# RF08.net
KiCad netlist of a schematic drawn in EAGLE
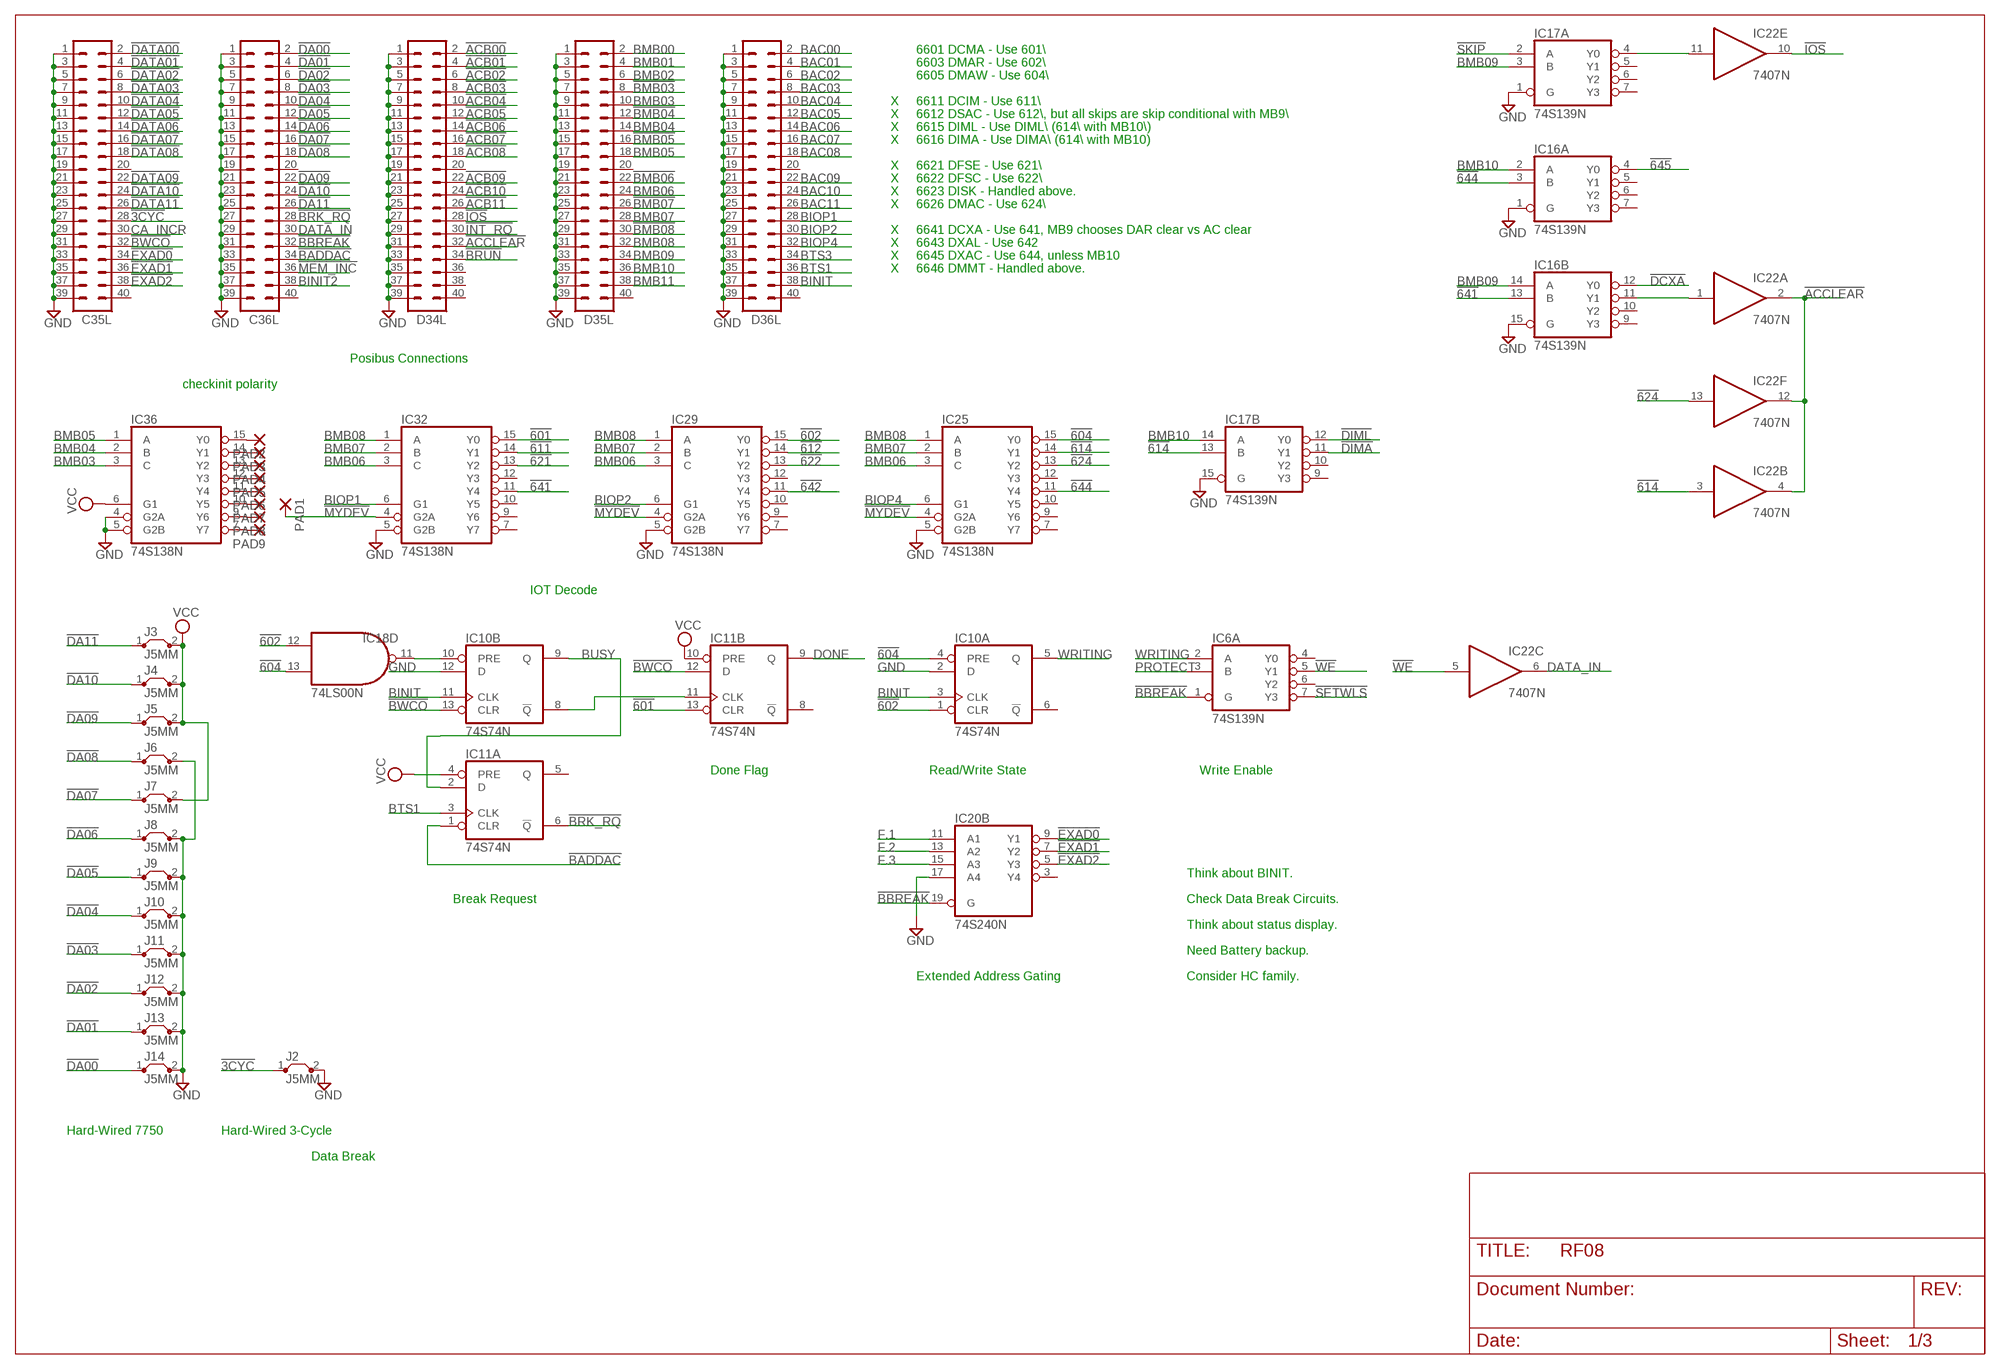
[diagram p0: schematic, sheet 1]
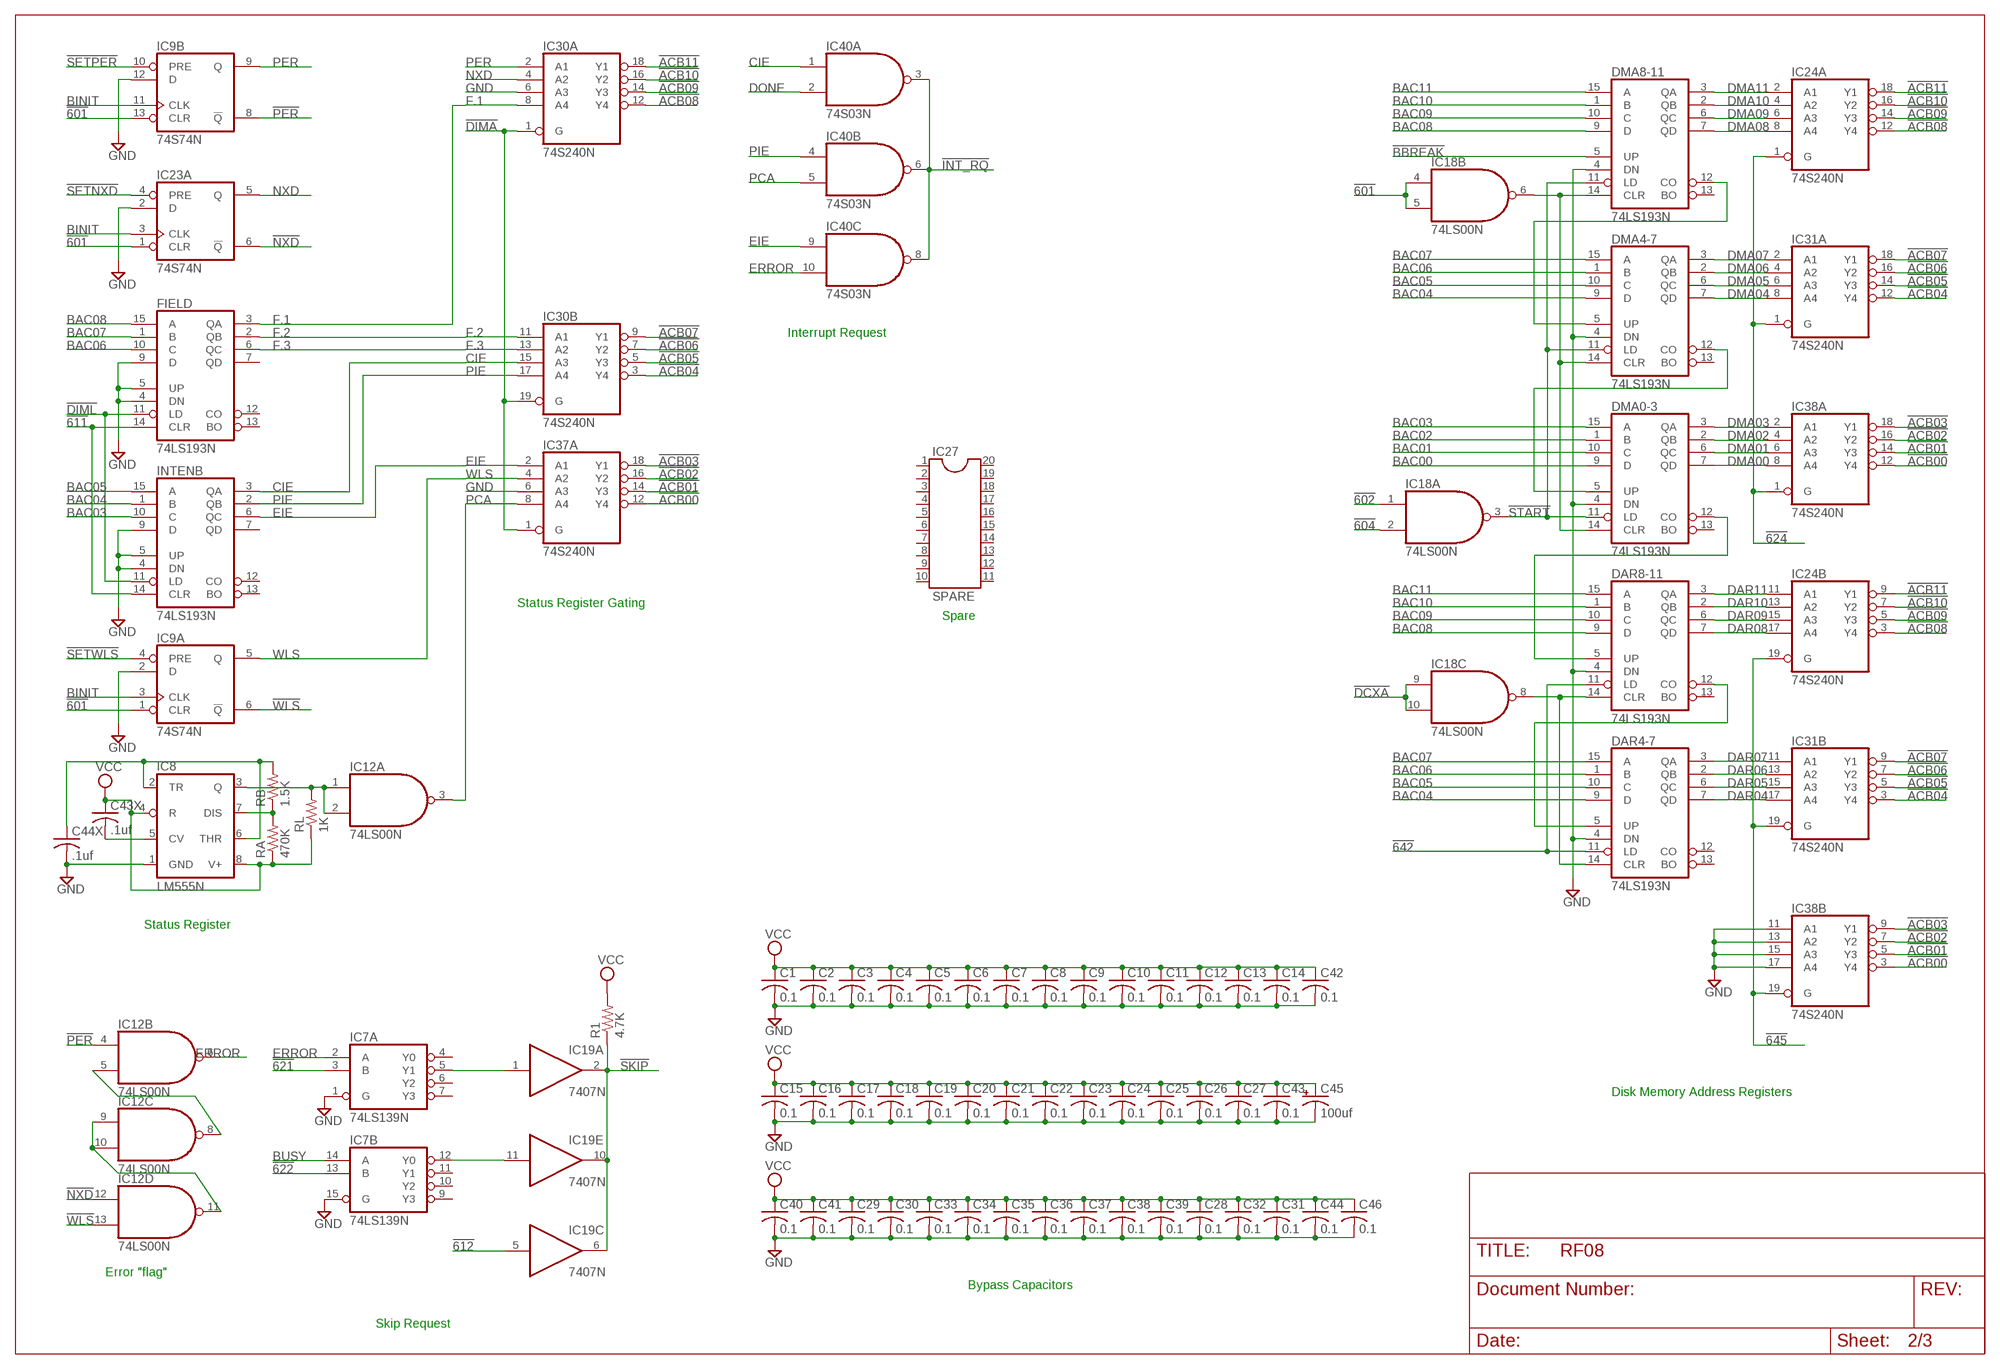
[diagram p1: schematic, sheet 2]
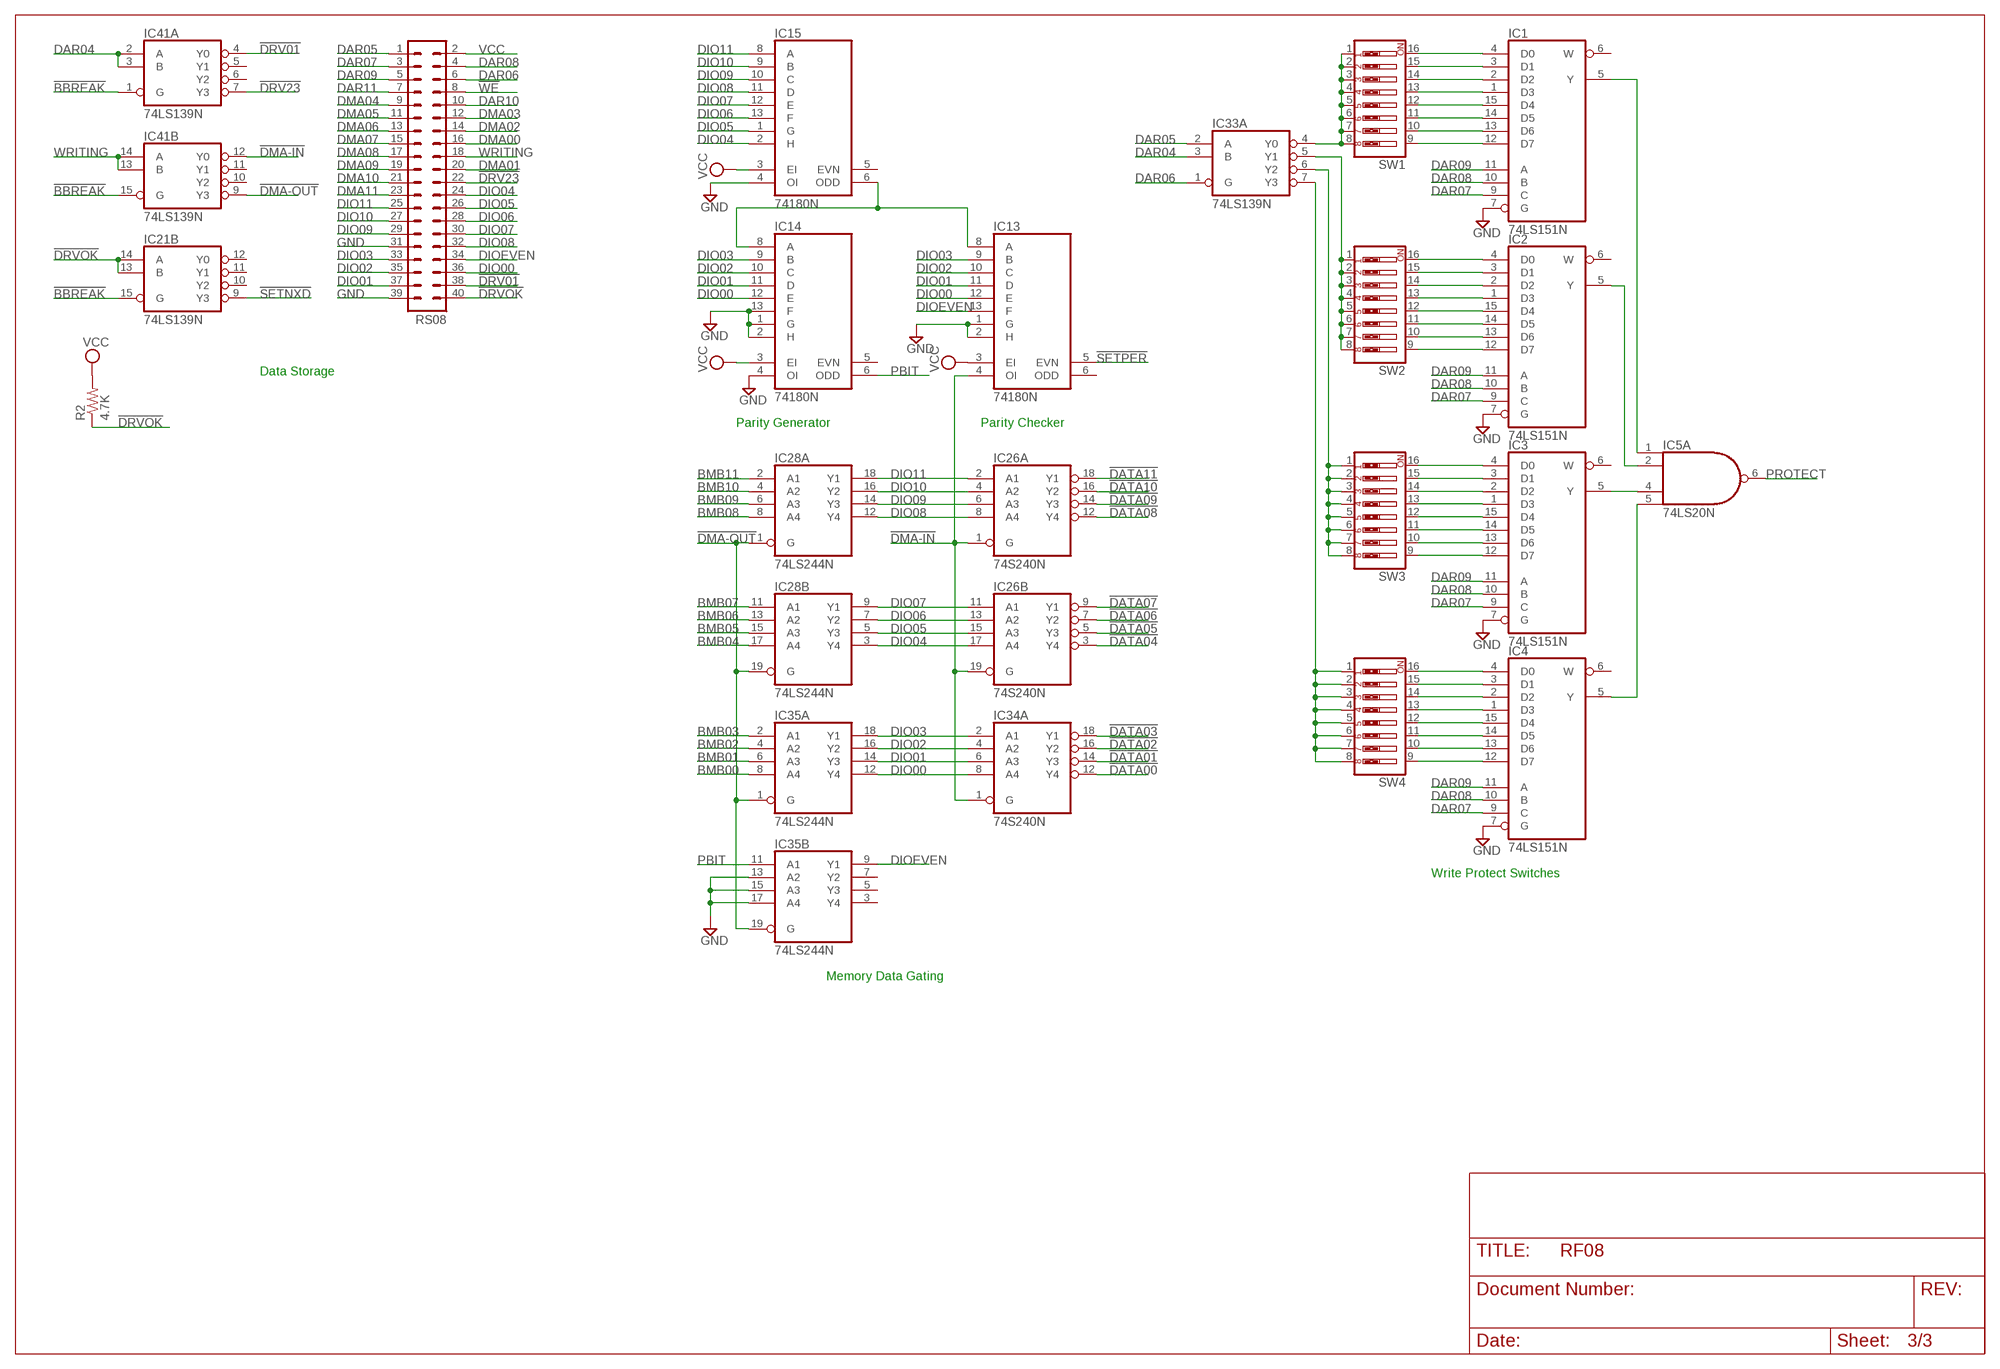
[diagram p2: schematic, sheet 3]

(export (version "E")
  (design (tool "Eeschema 10.0.6"))
  (components
    (comp (ref "C1")
      (value "0.1")
      (footprint "eagle-import:C050-025X075")
      (libsource (lib "eagle-import") (part "C-US050-025X075"))
    )
    (comp (ref "C2")
      (value "0.1")
      (footprint "eagle-import:C050-025X075")
      (libsource (lib "eagle-import") (part "C-US050-025X075"))
    )
    (comp (ref "C3")
      (value "0.1")
      (footprint "eagle-import:C050-025X075")
      (libsource (lib "eagle-import") (part "C-US050-025X075"))
    )
    (comp (ref "C4")
      (value "0.1")
      (footprint "eagle-import:C050-025X075")
      (libsource (lib "eagle-import") (part "C-US050-025X075"))
    )
    (comp (ref "C5")
      (value "0.1")
      (footprint "eagle-import:C050-025X075")
      (libsource (lib "eagle-import") (part "C-US050-025X075"))
    )
    (comp (ref "C6")
      (value "0.1")
      (footprint "eagle-import:C050-025X075")
      (libsource (lib "eagle-import") (part "C-US050-025X075"))
    )
    (comp (ref "C7")
      (value "0.1")
      (footprint "eagle-import:C050-025X075")
      (libsource (lib "eagle-import") (part "C-US050-025X075"))
    )
    (comp (ref "C8")
      (value "0.1")
      (footprint "eagle-import:C050-025X075")
      (libsource (lib "eagle-import") (part "C-US050-025X075"))
    )
    (comp (ref "C9")
      (value "0.1")
      (footprint "eagle-import:C050-025X075")
      (libsource (lib "eagle-import") (part "C-US050-025X075"))
    )
    (comp (ref "C10")
      (value "0.1")
      (footprint "eagle-import:C050-025X075")
      (libsource (lib "eagle-import") (part "C-US050-025X075"))
    )
    (comp (ref "C11")
      (value "0.1")
      (footprint "eagle-import:C050-025X075")
      (libsource (lib "eagle-import") (part "C-US050-025X075"))
    )
    (comp (ref "C12")
      (value "0.1")
      (footprint "eagle-import:C050-025X075")
      (libsource (lib "eagle-import") (part "C-US050-025X075"))
    )
    (comp (ref "C13")
      (value "0.1")
      (footprint "eagle-import:C050-025X075")
      (libsource (lib "eagle-import") (part "C-US050-025X075"))
    )
    (comp (ref "C14")
      (value "0.1")
      (footprint "eagle-import:C050-025X075")
      (libsource (lib "eagle-import") (part "C-US050-025X075"))
    )
    (comp (ref "C15")
      (value "0.1")
      (footprint "eagle-import:C050-025X075")
      (libsource (lib "eagle-import") (part "C-US050-025X075"))
    )
    (comp (ref "C16")
      (value "0.1")
      (footprint "eagle-import:C050-025X075")
      (libsource (lib "eagle-import") (part "C-US050-025X075"))
    )
    (comp (ref "C17")
      (value "0.1")
      (footprint "eagle-import:C050-025X075")
      (libsource (lib "eagle-import") (part "C-US050-025X075"))
    )
    (comp (ref "C18")
      (value "0.1")
      (footprint "eagle-import:C050-025X075")
      (libsource (lib "eagle-import") (part "C-US050-025X075"))
    )
    (comp (ref "C19")
      (value "0.1")
      (footprint "eagle-import:C050-025X075")
      (libsource (lib "eagle-import") (part "C-US050-025X075"))
    )
    (comp (ref "C20")
      (value "0.1")
      (footprint "eagle-import:C050-025X075")
      (libsource (lib "eagle-import") (part "C-US050-025X075"))
    )
    (comp (ref "C21")
      (value "0.1")
      (footprint "eagle-import:C050-025X075")
      (libsource (lib "eagle-import") (part "C-US050-025X075"))
    )
    (comp (ref "C22")
      (value "0.1")
      (footprint "eagle-import:C050-025X075")
      (libsource (lib "eagle-import") (part "C-US050-025X075"))
    )
    (comp (ref "C23")
      (value "0.1")
      (footprint "eagle-import:C050-025X075")
      (libsource (lib "eagle-import") (part "C-US050-025X075"))
    )
    (comp (ref "C24")
      (value "0.1")
      (footprint "eagle-import:C050-025X075")
      (libsource (lib "eagle-import") (part "C-US050-025X075"))
    )
    (comp (ref "C25")
      (value "0.1")
      (footprint "eagle-import:C050-025X075")
      (libsource (lib "eagle-import") (part "C-US050-025X075"))
    )
    (comp (ref "C26")
      (value "0.1")
      (footprint "eagle-import:C050-025X075")
      (libsource (lib "eagle-import") (part "C-US050-025X075"))
    )
    (comp (ref "C27")
      (value "0.1")
      (footprint "eagle-import:C050-025X075")
      (libsource (lib "eagle-import") (part "C-US050-025X075"))
    )
    (comp (ref "C28")
      (value "0.1")
      (footprint "eagle-import:C050-025X075")
      (libsource (lib "eagle-import") (part "C-US050-025X075"))
    )
    (comp (ref "C29")
      (value "0.1")
      (footprint "eagle-import:C050-025X075")
      (libsource (lib "eagle-import") (part "C-US050-025X075"))
    )
    (comp (ref "C30")
      (value "0.1")
      (footprint "eagle-import:C050-025X075")
      (libsource (lib "eagle-import") (part "C-US050-025X075"))
    )
    (comp (ref "C31")
      (value "0.1")
      (footprint "eagle-import:C050-025X075")
      (libsource (lib "eagle-import") (part "C-US050-025X075"))
    )
    (comp (ref "C32")
      (value "0.1")
      (footprint "eagle-import:C050-025X075")
      (libsource (lib "eagle-import") (part "C-US050-025X075"))
    )
    (comp (ref "C33")
      (value "0.1")
      (footprint "eagle-import:C050-025X075")
      (libsource (lib "eagle-import") (part "C-US050-025X075"))
    )
    (comp (ref "C34")
      (value "0.1")
      (footprint "eagle-import:C050-025X075")
      (libsource (lib "eagle-import") (part "C-US050-025X075"))
    )
    (comp (ref "C35")
      (value "0.1")
      (footprint "eagle-import:C050-025X075")
      (libsource (lib "eagle-import") (part "C-US050-025X075"))
    )
    (comp (ref "C36")
      (value "0.1")
      (footprint "eagle-import:C050-025X075")
      (libsource (lib "eagle-import") (part "C-US050-025X075"))
    )
    (comp (ref "C37")
      (value "0.1")
      (footprint "eagle-import:C050-025X075")
      (libsource (lib "eagle-import") (part "C-US050-025X075"))
    )
    (comp (ref "C38")
      (value "0.1")
      (footprint "eagle-import:C050-025X075")
      (libsource (lib "eagle-import") (part "C-US050-025X075"))
    )
    (comp (ref "C39")
      (value "0.1")
      (footprint "eagle-import:C050-025X075")
      (libsource (lib "eagle-import") (part "C-US050-025X075"))
    )
    (comp (ref "C40")
      (value "0.1")
      (footprint "eagle-import:C050-025X075")
      (libsource (lib "eagle-import") (part "C-US050-025X075"))
    )
    (comp (ref "C41")
      (value "0.1")
      (footprint "eagle-import:C050-025X075")
      (libsource (lib "eagle-import") (part "C-US050-025X075"))
    )
    (comp (ref "C42")
      (value "0.1")
      (footprint "eagle-import:C050-025X075")
      (libsource (lib "eagle-import") (part "C-US050-025X075"))
    )
    (comp (ref "C43")
      (value "0.1")
      (footprint "eagle-import:C050-025X075")
      (libsource (lib "eagle-import") (part "C-US050-025X075"))
    )
    (comp (ref "C43X")
      (value ".1uf")
      (footprint "eagle-import:C050-025X075")
      (libsource (lib "eagle-import") (part "C-US050-025X075"))
    )
    (comp (ref "C44")
      (value "0.1")
      (footprint "eagle-import:C050-025X075")
      (libsource (lib "eagle-import") (part "C-US050-025X075"))
    )
    (comp (ref "C44X")
      (value ".1uf")
      (footprint "eagle-import:C050-025X075")
      (libsource (lib "eagle-import") (part "C-US050-025X075"))
    )
    (comp (ref "C45")
      (value "100uf")
      (footprint "eagle-import:E22-6")
      (libsource (lib "eagle-import") (part "CPOL-USE22-6AXIAL"))
    )
    (comp (ref "C46")
      (value "0.1")
      (footprint "eagle-import:C050-025X075")
      (libsource (lib "eagle-import") (part "C-US050-025X075"))
    )
    (comp (ref "DAR4-7")
      (value "74LS193N")
      (footprint "eagle-import:DIL16")
      (libsource (lib "eagle-import") (part "74192NLS"))
    )
    (comp (ref "DAR8-11")
      (value "74LS193N")
      (footprint "eagle-import:DIL16")
      (libsource (lib "eagle-import") (part "74192NLS"))
    )
    (comp (ref "DMA0-3")
      (value "74LS193N")
      (footprint "eagle-import:DIL16")
      (libsource (lib "eagle-import") (part "74192NLS"))
    )
    (comp (ref "DMA4-7")
      (value "74LS193N")
      (footprint "eagle-import:DIL16")
      (libsource (lib "eagle-import") (part "74192NLS"))
    )
    (comp (ref "DMA8-11")
      (value "74LS193N")
      (footprint "eagle-import:DIL16")
      (libsource (lib "eagle-import") (part "74192NLS"))
    )
    (comp (ref "FIELD")
      (value "74LS193N")
      (footprint "eagle-import:DIL16")
      (libsource (lib "eagle-import") (part "74192NLS"))
    )
    (comp (ref "IC7")
      (value "74LS139N")
      (footprint "eagle-import:DIL16")
      (libsource (lib "eagle-import") (part "74139NLS"))
    )
    (comp (ref "IC8")
      (value "LM555N")
      (footprint "eagle-import:DIL08")
      (libsource (lib "eagle-import") (part "555NLM"))
    )
    (comp (ref "IC9")
      (value "74S74N")
      (footprint "eagle-import:DIL14")
      (libsource (lib "eagle-import") (part "7474NS"))
    )
    (comp (ref "IC12")
      (value "74LS00N")
      (footprint "eagle-import:DIL14")
      (libsource (lib "eagle-import") (part "7400NLS"))
    )
    (comp (ref "IC18")
      (value "74LS00N")
      (footprint "eagle-import:DIL14")
      (libsource (lib "eagle-import") (part "7400NLS"))
    )
    (comp (ref "IC19")
      (value "7407N")
      (footprint "eagle-import:DIL14")
      (libsource (lib "eagle-import") (part "7407N"))
    )
    (comp (ref "IC23")
      (value "74S74N")
      (footprint "eagle-import:DIL14")
      (libsource (lib "eagle-import") (part "7474NS"))
    )
    (comp (ref "IC24")
      (value "74S240N")
      (footprint "eagle-import:DIL20")
      (libsource (lib "eagle-import") (part "74240NS"))
    )
    (comp (ref "IC27")
      (value "SPARE")
      (footprint "eagle-import:DIL20")
      (libsource (lib "eagle-import") (part "DIL20"))
    )
    (comp (ref "IC30")
      (value "74S240N")
      (footprint "eagle-import:DIL20")
      (libsource (lib "eagle-import") (part "74240NS"))
    )
    (comp (ref "IC31")
      (value "74S240N")
      (footprint "eagle-import:DIL20")
      (libsource (lib "eagle-import") (part "74240NS"))
    )
    (comp (ref "IC37")
      (value "74S240N")
      (footprint "eagle-import:DIL20")
      (libsource (lib "eagle-import") (part "74240NS"))
    )
    (comp (ref "IC38")
      (value "74S240N")
      (footprint "eagle-import:DIL20")
      (libsource (lib "eagle-import") (part "74240NS"))
    )
    (comp (ref "IC40")
      (value "74S03N")
      (footprint "eagle-import:DIL14")
      (libsource (lib "eagle-import") (part "7403NS"))
    )
    (comp (ref "INTENB")
      (value "74LS193N")
      (footprint "eagle-import:DIL16")
      (libsource (lib "eagle-import") (part "74192NLS"))
    )
    (comp (ref "R1")
      (value "4.7K")
      (footprint "eagle-import:0207_10")
      (libsource (lib "eagle-import") (part "R-US_0207/10"))
    )
    (comp (ref "RA")
      (value "470K")
      (footprint "eagle-import:0207_10")
      (libsource (lib "eagle-import") (part "R-US_0207/10"))
    )
    (comp (ref "RB")
      (value "1.5K")
      (footprint "eagle-import:0207_10")
      (libsource (lib "eagle-import") (part "R-US_0207/10"))
    )
    (comp (ref "RL")
      (value "1K")
      (footprint "eagle-import:0207_10")
      (libsource (lib "eagle-import") (part "R-US_0207/10"))
    )
    (comp (ref "IC1")
      (value "74LS151N")
      (footprint "eagle-import:DIL16")
      (libsource (lib "eagle-import") (part "74151NLS"))
    )
    (comp (ref "IC2")
      (value "74LS151N")
      (footprint "eagle-import:DIL16")
      (libsource (lib "eagle-import") (part "74151NLS"))
    )
    (comp (ref "IC3")
      (value "74LS151N")
      (footprint "eagle-import:DIL16")
      (libsource (lib "eagle-import") (part "74151NLS"))
    )
    (comp (ref "IC4")
      (value "74LS151N")
      (footprint "eagle-import:DIL16")
      (libsource (lib "eagle-import") (part "74151NLS"))
    )
    (comp (ref "IC5")
      (value "74LS20N")
      (footprint "eagle-import:DIL14")
      (libsource (lib "eagle-import") (part "7420NLS"))
    )
    (comp (ref "IC13")
      (value "74180N")
      (footprint "eagle-import:DIL14")
      (libsource (lib "eagle-import") (part "74180N"))
    )
    (comp (ref "IC14")
      (value "74180N")
      (footprint "eagle-import:DIL14")
      (libsource (lib "eagle-import") (part "74180N"))
    )
    (comp (ref "IC15")
      (value "74180N")
      (footprint "eagle-import:DIL14")
      (libsource (lib "eagle-import") (part "74180N"))
    )
    (comp (ref "IC21")
      (value "74LS139N")
      (footprint "eagle-import:DIL16")
      (libsource (lib "eagle-import") (part "74139NLS"))
    )
    (comp (ref "IC26")
      (value "74S240N")
      (footprint "eagle-import:DIL20")
      (libsource (lib "eagle-import") (part "74240NS"))
    )
    (comp (ref "IC28")
      (value "74LS244N")
      (footprint "eagle-import:DIL20")
      (libsource (lib "eagle-import") (part "74244NLS"))
    )
    (comp (ref "IC33")
      (value "74LS139N")
      (footprint "eagle-import:DIL16")
      (libsource (lib "eagle-import") (part "74139NLS"))
    )
    (comp (ref "IC34")
      (value "74S240N")
      (footprint "eagle-import:DIL20")
      (libsource (lib "eagle-import") (part "74240NS"))
    )
    (comp (ref "IC35")
      (value "74LS244N")
      (footprint "eagle-import:DIL20")
      (libsource (lib "eagle-import") (part "74244NLS"))
    )
    (comp (ref "IC41")
      (value "74LS139N")
      (footprint "eagle-import:DIL16")
      (libsource (lib "eagle-import") (part "74139NLS"))
    )
    (comp (ref "R2")
      (value "4.7K")
      (footprint "eagle-import:0207_10")
      (libsource (lib "eagle-import") (part "R-US_0207/10"))
    )
    (comp (ref "RS08")
      (value "MA20-2")
      (footprint "eagle-import:MA20-2")
      (libsource (lib "eagle-import") (part "MA20-2"))
    )
    (comp (ref "SW1")
      (value "SW_DIP-8")
      (footprint "eagle-import:EDG-08")
      (libsource (lib "eagle-import") (part "SW_DIP-8"))
    )
    (comp (ref "SW2")
      (value "SW_DIP-8")
      (footprint "eagle-import:EDG-08")
      (libsource (lib "eagle-import") (part "SW_DIP-8"))
    )
    (comp (ref "SW3")
      (value "SW_DIP-8")
      (footprint "eagle-import:EDG-08")
      (libsource (lib "eagle-import") (part "SW_DIP-8"))
    )
    (comp (ref "SW4")
      (value "SW_DIP-8")
      (footprint "eagle-import:EDG-08")
      (libsource (lib "eagle-import") (part "SW_DIP-8"))
    )
    (comp (ref "C35L")
      (value "MA20-2")
      (footprint "eagle-import:MA20-2")
      (libsource (lib "eagle-import") (part "MA20-2"))
    )
    (comp (ref "C36L")
      (value "MA20-2")
      (footprint "eagle-import:MA20-2")
      (libsource (lib "eagle-import") (part "MA20-2"))
    )
    (comp (ref "D34L")
      (value "MA20-2")
      (footprint "eagle-import:MA20-2")
      (libsource (lib "eagle-import") (part "MA20-2"))
    )
    (comp (ref "D35L")
      (value "MA20-2")
      (footprint "eagle-import:MA20-2")
      (libsource (lib "eagle-import") (part "MA20-2"))
    )
    (comp (ref "D36L")
      (value "MA20-2")
      (footprint "eagle-import:MA20-2")
      (libsource (lib "eagle-import") (part "MA20-2"))
    )
    (comp (ref "IC6")
      (value "74S139N")
      (footprint "eagle-import:DIL16")
      (libsource (lib "eagle-import") (part "74139NS"))
    )
    (comp (ref "IC10")
      (value "74S74N")
      (footprint "eagle-import:DIL14")
      (libsource (lib "eagle-import") (part "7474NS"))
    )
    (comp (ref "IC11")
      (value "74S74N")
      (footprint "eagle-import:DIL14")
      (libsource (lib "eagle-import") (part "7474NS"))
    )
    (comp (ref "IC16")
      (value "74S139N")
      (footprint "eagle-import:DIL16")
      (libsource (lib "eagle-import") (part "74139NS"))
    )
    (comp (ref "IC17")
      (value "74S139N")
      (footprint "eagle-import:DIL16")
      (libsource (lib "eagle-import") (part "74139NS"))
    )
    (comp (ref "IC20")
      (value "74S240N")
      (footprint "eagle-import:DIL20")
      (libsource (lib "eagle-import") (part "74240NS"))
    )
    (comp (ref "IC22")
      (value "7407N")
      (footprint "eagle-import:DIL14")
      (libsource (lib "eagle-import") (part "7407N"))
    )
    (comp (ref "IC25")
      (value "74S138N")
      (footprint "eagle-import:DIL16")
      (libsource (lib "eagle-import") (part "74138NS"))
    )
    (comp (ref "IC29")
      (value "74S138N")
      (footprint "eagle-import:DIL16")
      (libsource (lib "eagle-import") (part "74138NS"))
    )
    (comp (ref "IC32")
      (value "74S138N")
      (footprint "eagle-import:DIL16")
      (libsource (lib "eagle-import") (part "74138NS"))
    )
    (comp (ref "IC36")
      (value "74S138N")
      (footprint "eagle-import:DIL16")
      (libsource (lib "eagle-import") (part "74138NS"))
    )
    (comp (ref "J2")
      (value "J5MM")
      (footprint "eagle-import:05")
      (libsource (lib "eagle-import") (part "J5MM"))
    )
    (comp (ref "J3")
      (value "J5MM")
      (footprint "eagle-import:05")
      (libsource (lib "eagle-import") (part "J5MM"))
    )
    (comp (ref "J4")
      (value "J5MM")
      (footprint "eagle-import:05")
      (libsource (lib "eagle-import") (part "J5MM"))
    )
    (comp (ref "J5")
      (value "J5MM")
      (footprint "eagle-import:05")
      (libsource (lib "eagle-import") (part "J5MM"))
    )
    (comp (ref "J6")
      (value "J5MM")
      (footprint "eagle-import:05")
      (libsource (lib "eagle-import") (part "J5MM"))
    )
    (comp (ref "J7")
      (value "J5MM")
      (footprint "eagle-import:05")
      (libsource (lib "eagle-import") (part "J5MM"))
    )
    (comp (ref "J8")
      (value "J5MM")
      (footprint "eagle-import:05")
      (libsource (lib "eagle-import") (part "J5MM"))
    )
    (comp (ref "J9")
      (value "J5MM")
      (footprint "eagle-import:05")
      (libsource (lib "eagle-import") (part "J5MM"))
    )
    (comp (ref "J10")
      (value "J5MM")
      (footprint "eagle-import:05")
      (libsource (lib "eagle-import") (part "J5MM"))
    )
    (comp (ref "J11")
      (value "J5MM")
      (footprint "eagle-import:05")
      (libsource (lib "eagle-import") (part "J5MM"))
    )
    (comp (ref "J12")
      (value "J5MM")
      (footprint "eagle-import:05")
      (libsource (lib "eagle-import") (part "J5MM"))
    )
    (comp (ref "J13")
      (value "J5MM")
      (footprint "eagle-import:05")
      (libsource (lib "eagle-import") (part "J5MM"))
    )
    (comp (ref "J14")
      (value "J5MM")
      (footprint "eagle-import:05")
      (libsource (lib "eagle-import") (part "J5MM"))
    )
    (comp (ref "PAD1")
      (value "1,6/0,8")
      (footprint "eagle-import:1,6_0,8")
      (libsource (lib "eagle-import") (part "1,6/0,8"))
    )
    (comp (ref "PAD2")
      (value "1,6/0,8")
      (footprint "eagle-import:1,6_0,8")
      (libsource (lib "eagle-import") (part "1,6/0,8"))
    )
    (comp (ref "PAD3")
      (value "1,6/0,8")
      (footprint "eagle-import:1,6_0,8")
      (libsource (lib "eagle-import") (part "1,6/0,8"))
    )
    (comp (ref "PAD4")
      (value "1,6/0,8")
      (footprint "eagle-import:1,6_0,8")
      (libsource (lib "eagle-import") (part "1,6/0,8"))
    )
    (comp (ref "PAD5")
      (value "1,6/0,8")
      (footprint "eagle-import:1,6_0,8")
      (libsource (lib "eagle-import") (part "1,6/0,8"))
    )
    (comp (ref "PAD6")
      (value "1,6/0,8")
      (footprint "eagle-import:1,6_0,8")
      (libsource (lib "eagle-import") (part "1,6/0,8"))
    )
    (comp (ref "PAD7")
      (value "1,6/0,8")
      (footprint "eagle-import:1,6_0,8")
      (libsource (lib "eagle-import") (part "1,6/0,8"))
    )
    (comp (ref "PAD8")
      (value "1,6/0,8")
      (footprint "eagle-import:1,6_0,8")
      (libsource (lib "eagle-import") (part "1,6/0,8"))
    )
    (comp (ref "PAD9")
      (value "1,6/0,8")
      (footprint "eagle-import:1,6_0,8")
      (libsource (lib "eagle-import") (part "1,6/0,8"))
    )
  )
  (nets
    (net (code "1") (name "BAC00") (class "Default")
      (node (ref "D36L") (pin "2") (pinfunction "2_2") (pintype "passive"))
      (node (ref "DMA0-3") (pin "9") (pinfunction "D_9") (pintype "input"))
    )
    (net (code "2") (name "BAC01") (class "Default")
      (node (ref "D36L") (pin "4") (pinfunction "4_4") (pintype "passive"))
      (node (ref "DMA0-3") (pin "10") (pinfunction "C_10") (pintype "input"))
    )
    (net (code "3") (name "BAC02") (class "Default")
      (node (ref "D36L") (pin "6") (pinfunction "6_6") (pintype "passive"))
      (node (ref "DMA0-3") (pin "1") (pinfunction "B_1") (pintype "input"))
    )
    (net (code "4") (name "BAC03") (class "Default")
      (node (ref "D36L") (pin "8") (pinfunction "8_8") (pintype "passive"))
      (node (ref "DMA0-3") (pin "15") (pinfunction "A_15") (pintype "input"))
      (node (ref "INTENB") (pin "10") (pinfunction "C_10") (pintype "input"))
    )
    (net (code "5") (name "BAC04") (class "Default")
      (node (ref "D36L") (pin "10") (pinfunction "10_10") (pintype "passive"))
      (node (ref "DAR4-7") (pin "9") (pinfunction "D_9") (pintype "input"))
      (node (ref "DMA4-7") (pin "9") (pinfunction "D_9") (pintype "input"))
      (node (ref "INTENB") (pin "1") (pinfunction "B_1") (pintype "input"))
    )
    (net (code "6") (name "BAC05") (class "Default")
      (node (ref "D36L") (pin "12") (pinfunction "12_12") (pintype "passive"))
      (node (ref "DAR4-7") (pin "10") (pinfunction "C_10") (pintype "input"))
      (node (ref "DMA4-7") (pin "10") (pinfunction "C_10") (pintype "input"))
      (node (ref "INTENB") (pin "15") (pinfunction "A_15") (pintype "input"))
    )
    (net (code "7") (name "BAC06") (class "Default")
      (node (ref "D36L") (pin "14") (pinfunction "14_14") (pintype "passive"))
      (node (ref "DAR4-7") (pin "1") (pinfunction "B_1") (pintype "input"))
      (node (ref "DMA4-7") (pin "1") (pinfunction "B_1") (pintype "input"))
      (node (ref "FIELD") (pin "10") (pinfunction "C_10") (pintype "input"))
    )
    (net (code "8") (name "BAC07") (class "Default")
      (node (ref "D36L") (pin "16") (pinfunction "16_16") (pintype "passive"))
      (node (ref "DAR4-7") (pin "15") (pinfunction "A_15") (pintype "input"))
      (node (ref "DMA4-7") (pin "15") (pinfunction "A_15") (pintype "input"))
      (node (ref "FIELD") (pin "1") (pinfunction "B_1") (pintype "input"))
    )
    (net (code "9") (name "BAC08") (class "Default")
      (node (ref "D36L") (pin "18") (pinfunction "18_18") (pintype "passive"))
      (node (ref "DAR8-11") (pin "9") (pinfunction "D_9") (pintype "input"))
      (node (ref "DMA8-11") (pin "9") (pinfunction "D_9") (pintype "input"))
      (node (ref "FIELD") (pin "15") (pinfunction "A_15") (pintype "input"))
    )
    (net (code "10") (name "BAC09") (class "Default")
      (node (ref "D36L") (pin "22") (pinfunction "22_22") (pintype "passive"))
      (node (ref "DAR8-11") (pin "10") (pinfunction "C_10") (pintype "input"))
      (node (ref "DMA8-11") (pin "10") (pinfunction "C_10") (pintype "input"))
    )
    (net (code "11") (name "BAC10") (class "Default")
      (node (ref "D36L") (pin "24") (pinfunction "24_24") (pintype "passive"))
      (node (ref "DAR8-11") (pin "1") (pinfunction "B_1") (pintype "input"))
      (node (ref "DMA8-11") (pin "1") (pinfunction "B_1") (pintype "input"))
    )
    (net (code "12") (name "BAC11") (class "Default")
      (node (ref "D36L") (pin "26") (pinfunction "26_26") (pintype "passive"))
      (node (ref "DAR8-11") (pin "15") (pinfunction "A_15") (pintype "input"))
      (node (ref "DMA8-11") (pin "15") (pinfunction "A_15") (pintype "input"))
    )
    (net (code "13") (name "BINIT") (class "Default")
      (node (ref "D36L") (pin "38") (pinfunction "38_38") (pintype "passive"))
      (node (ref "IC10") (pin "11") (pinfunction "CLK_11") (pintype "input"))
      (node (ref "IC10") (pin "3") (pinfunction "CLK_3") (pintype "input"))
      (node (ref "IC23") (pin "3") (pinfunction "CLK_3") (pintype "input"))
      (node (ref "IC9") (pin "11") (pinfunction "CLK_11") (pintype "input"))
      (node (ref "IC9") (pin "3") (pinfunction "CLK_3") (pintype "input"))
    )
    (net (code "14") (name "BINIT2") (class "Default")
      (node (ref "C36L") (pin "38") (pinfunction "38_38") (pintype "passive"))
    )
    (net (code "15") (name "BIOP1") (class "Default")
      (node (ref "D36L") (pin "28") (pinfunction "28_28") (pintype "passive"))
      (node (ref "IC32") (pin "6") (pinfunction "G1_6") (pintype "input"))
    )
    (net (code "16") (name "BIOP2") (class "Default")
      (node (ref "D36L") (pin "30") (pinfunction "30_30") (pintype "passive"))
      (node (ref "IC29") (pin "6") (pinfunction "G1_6") (pintype "input"))
    )
    (net (code "17") (name "BIOP4") (class "Default")
      (node (ref "D36L") (pin "32") (pinfunction "32_32") (pintype "passive"))
      (node (ref "IC25") (pin "6") (pinfunction "G1_6") (pintype "input"))
    )
    (net (code "18") (name "BMB00") (class "Default")
      (node (ref "D35L") (pin "2") (pinfunction "2_2") (pintype "passive"))
      (node (ref "IC35") (pin "8") (pinfunction "A4_8") (pintype "input"))
    )
    (net (code "19") (name "BMB01") (class "Default")
      (node (ref "D35L") (pin "4") (pinfunction "4_4") (pintype "passive"))
      (node (ref "IC35") (pin "6") (pinfunction "A3_6") (pintype "input"))
    )
    (net (code "20") (name "BMB02") (class "Default")
      (node (ref "D35L") (pin "6") (pinfunction "6_6") (pintype "passive"))
      (node (ref "IC35") (pin "4") (pinfunction "A2_4") (pintype "input"))
    )
    (net (code "21") (name "BMB03") (class "Default")
      (node (ref "D35L") (pin "10") (pinfunction "10_10") (pintype "passive"))
      (node (ref "IC35") (pin "2") (pinfunction "A1_2") (pintype "input"))
      (node (ref "IC36") (pin "3") (pinfunction "C_3") (pintype "input"))
    )
    (net (code "22") (name "BMB04") (class "Default")
      (node (ref "D35L") (pin "14") (pinfunction "14_14") (pintype "passive"))
      (node (ref "IC28") (pin "17") (pinfunction "A4_17") (pintype "input"))
      (node (ref "IC36") (pin "2") (pinfunction "B_2") (pintype "input"))
    )
    (net (code "23") (name "BMB05") (class "Default")
      (node (ref "D35L") (pin "18") (pinfunction "18_18") (pintype "passive"))
      (node (ref "IC28") (pin "15") (pinfunction "A3_15") (pintype "input"))
      (node (ref "IC36") (pin "1") (pinfunction "A_1") (pintype "input"))
    )
    (net (code "24") (name "BMB06") (class "Default")
      (node (ref "D35L") (pin "24") (pinfunction "24_24") (pintype "passive"))
      (node (ref "IC25") (pin "3") (pinfunction "C_3") (pintype "input"))
      (node (ref "IC28") (pin "13") (pinfunction "A2_13") (pintype "input"))
      (node (ref "IC29") (pin "3") (pinfunction "C_3") (pintype "input"))
      (node (ref "IC32") (pin "3") (pinfunction "C_3") (pintype "input"))
    )
    (net (code "25") (name "BMB07") (class "Default")
      (node (ref "D35L") (pin "28") (pinfunction "28_28") (pintype "passive"))
      (node (ref "IC25") (pin "2") (pinfunction "B_2") (pintype "input"))
      (node (ref "IC28") (pin "11") (pinfunction "A1_11") (pintype "input"))
      (node (ref "IC29") (pin "2") (pinfunction "B_2") (pintype "input"))
      (node (ref "IC32") (pin "2") (pinfunction "B_2") (pintype "input"))
    )
    (net (code "26") (name "BMB08") (class "Default")
      (node (ref "D35L") (pin "32") (pinfunction "32_32") (pintype "passive"))
      (node (ref "IC25") (pin "1") (pinfunction "A_1") (pintype "input"))
      (node (ref "IC28") (pin "8") (pinfunction "A4_8") (pintype "input"))
      (node (ref "IC29") (pin "1") (pinfunction "A_1") (pintype "input"))
      (node (ref "IC32") (pin "1") (pinfunction "A_1") (pintype "input"))
    )
    (net (code "27") (name "BMB09") (class "Default")
      (node (ref "D35L") (pin "34") (pinfunction "34_34") (pintype "passive"))
      (node (ref "IC16") (pin "14") (pinfunction "A_14") (pintype "input"))
      (node (ref "IC17") (pin "3") (pinfunction "B_3") (pintype "input"))
      (node (ref "IC28") (pin "6") (pinfunction "A3_6") (pintype "input"))
    )
    (net (code "28") (name "BMB10") (class "Default")
      (node (ref "D35L") (pin "36") (pinfunction "36_36") (pintype "passive"))
      (node (ref "IC16") (pin "2") (pinfunction "A_2") (pintype "input"))
      (node (ref "IC17") (pin "14") (pinfunction "A_14") (pintype "input"))
      (node (ref "IC28") (pin "4") (pinfunction "A2_4") (pintype "input"))
    )
    (net (code "29") (name "BMB11") (class "Default")
      (node (ref "D35L") (pin "38") (pinfunction "38_38") (pintype "passive"))
      (node (ref "IC28") (pin "2") (pinfunction "A1_2") (pintype "input"))
    )
    (net (code "30") (name "BTS1") (class "Default")
      (node (ref "D36L") (pin "36") (pinfunction "36_36") (pintype "passive"))
      (node (ref "IC11") (pin "3") (pinfunction "CLK_3") (pintype "input"))
    )
    (net (code "31") (name "BTS3") (class "Default")
      (node (ref "D36L") (pin "34") (pinfunction "34_34") (pintype "passive"))
    )
    (net (code "32") (name "BUSY") (class "Default")
      (node (ref "IC10") (pin "9") (pinfunction "Q_9") (pintype "output"))
      (node (ref "IC11") (pin "2") (pinfunction "D_2") (pintype "input"))
      (node (ref "IC7") (pin "14") (pinfunction "A_14") (pintype "input"))
    )
    (net (code "33") (name "CA_INCR") (class "Default")
      (node (ref "C35L") (pin "30") (pinfunction "30_30") (pintype "passive"))
    )
    (net (code "34") (name "CIE") (class "Default")
      (node (ref "IC30") (pin "15") (pinfunction "A3_15") (pintype "input"))
      (node (ref "IC40") (pin "1") (pinfunction "I0_1") (pintype "input"))
      (node (ref "INTENB") (pin "3") (pinfunction "QA_3") (pintype "output"))
    )
    (net (code "35") (name "DAR04") (class "Default")
      (node (ref "DAR4-7") (pin "7") (pinfunction "QD_7") (pintype "output"))
      (node (ref "IC31") (pin "17") (pinfunction "A4_17") (pintype "input"))
      (node (ref "IC33") (pin "3") (pinfunction "B_3") (pintype "input"))
      (node (ref "IC41") (pin "2") (pinfunction "A_2") (pintype "input"))
      (node (ref "IC41") (pin "3") (pinfunction "B_3") (pintype "input"))
    )
    (net (code "36") (name "DAR05") (class "Default")
      (node (ref "DAR4-7") (pin "6") (pinfunction "QC_6") (pintype "output"))
      (node (ref "IC31") (pin "15") (pinfunction "A3_15") (pintype "input"))
      (node (ref "IC33") (pin "2") (pinfunction "A_2") (pintype "input"))
      (node (ref "RS08") (pin "1") (pinfunction "1_1") (pintype "passive"))
    )
    (net (code "37") (name "DAR06") (class "Default")
      (node (ref "DAR4-7") (pin "2") (pinfunction "QB_2") (pintype "output"))
      (node (ref "IC31") (pin "13") (pinfunction "A2_13") (pintype "input"))
      (node (ref "IC33") (pin "1") (pinfunction "G_1") (pintype "input"))
      (node (ref "RS08") (pin "6") (pinfunction "6_6") (pintype "passive"))
    )
    (net (code "38") (name "DAR07") (class "Default")
      (node (ref "DAR4-7") (pin "3") (pinfunction "QA_3") (pintype "output"))
      (node (ref "IC1") (pin "9") (pinfunction "C_9") (pintype "input"))
      (node (ref "IC2") (pin "9") (pinfunction "C_9") (pintype "input"))
      (node (ref "IC3") (pin "9") (pinfunction "C_9") (pintype "input"))
      (node (ref "IC31") (pin "11") (pinfunction "A1_11") (pintype "input"))
      (node (ref "IC4") (pin "9") (pinfunction "C_9") (pintype "input"))
      (node (ref "RS08") (pin "3") (pinfunction "3_3") (pintype "passive"))
    )
    (net (code "39") (name "DAR08") (class "Default")
      (node (ref "DAR8-11") (pin "7") (pinfunction "QD_7") (pintype "output"))
      (node (ref "IC1") (pin "10") (pinfunction "B_10") (pintype "input"))
      (node (ref "IC2") (pin "10") (pinfunction "B_10") (pintype "input"))
      (node (ref "IC24") (pin "17") (pinfunction "A4_17") (pintype "input"))
      (node (ref "IC3") (pin "10") (pinfunction "B_10") (pintype "input"))
      (node (ref "IC4") (pin "10") (pinfunction "B_10") (pintype "input"))
      (node (ref "RS08") (pin "4") (pinfunction "4_4") (pintype "passive"))
    )
    (net (code "40") (name "DAR09") (class "Default")
      (node (ref "DAR8-11") (pin "6") (pinfunction "QC_6") (pintype "output"))
      (node (ref "IC1") (pin "11") (pinfunction "A_11") (pintype "input"))
      (node (ref "IC2") (pin "11") (pinfunction "A_11") (pintype "input"))
      (node (ref "IC24") (pin "15") (pinfunction "A3_15") (pintype "input"))
      (node (ref "IC3") (pin "11") (pinfunction "A_11") (pintype "input"))
      (node (ref "IC4") (pin "11") (pinfunction "A_11") (pintype "input"))
      (node (ref "RS08") (pin "5") (pinfunction "5_5") (pintype "passive"))
    )
    (net (code "41") (name "DAR10") (class "Default")
      (node (ref "DAR8-11") (pin "2") (pinfunction "QB_2") (pintype "output"))
      (node (ref "IC24") (pin "13") (pinfunction "A2_13") (pintype "input"))
      (node (ref "RS08") (pin "10") (pinfunction "10_10") (pintype "passive"))
    )
    (net (code "42") (name "DAR11") (class "Default")
      (node (ref "DAR8-11") (pin "3") (pinfunction "QA_3") (pintype "output"))
      (node (ref "IC24") (pin "11") (pinfunction "A1_11") (pintype "input"))
      (node (ref "RS08") (pin "7") (pinfunction "7_7") (pintype "passive"))
    )
    (net (code "43") (name "DATA_IN") (class "Default")
      (node (ref "C36L") (pin "30") (pinfunction "30_30") (pintype "passive"))
      (node (ref "IC22") (pin "6") (pinfunction "O_6") (pintype "open_collector"))
    )
    (net (code "44") (name "DIO00") (class "Default")
      (node (ref "IC13") (pin "12") (pinfunction "E_12") (pintype "input"))
      (node (ref "IC14") (pin "12") (pinfunction "E_12") (pintype "input"))
      (node (ref "IC34") (pin "8") (pinfunction "A4_8") (pintype "input"))
      (node (ref "IC35") (pin "12") (pinfunction "Y4_12") (pintype "tri_state"))
      (node (ref "RS08") (pin "36") (pinfunction "36_36") (pintype "passive"))
    )
    (net (code "45") (name "DIO01") (class "Default")
      (node (ref "IC13") (pin "11") (pinfunction "D_11") (pintype "input"))
      (node (ref "IC14") (pin "11") (pinfunction "D_11") (pintype "input"))
      (node (ref "IC34") (pin "6") (pinfunction "A3_6") (pintype "input"))
      (node (ref "IC35") (pin "14") (pinfunction "Y3_14") (pintype "tri_state"))
      (node (ref "RS08") (pin "37") (pinfunction "37_37") (pintype "passive"))
    )
    (net (code "46") (name "DIO02") (class "Default")
      (node (ref "IC13") (pin "10") (pinfunction "C_10") (pintype "input"))
      (node (ref "IC14") (pin "10") (pinfunction "C_10") (pintype "input"))
      (node (ref "IC34") (pin "4") (pinfunction "A2_4") (pintype "input"))
      (node (ref "IC35") (pin "16") (pinfunction "Y2_16") (pintype "tri_state"))
      (node (ref "RS08") (pin "35") (pinfunction "35_35") (pintype "passive"))
    )
    (net (code "47") (name "DIO03") (class "Default")
      (node (ref "IC13") (pin "9") (pinfunction "B_9") (pintype "input"))
      (node (ref "IC14") (pin "9") (pinfunction "B_9") (pintype "input"))
      (node (ref "IC34") (pin "2") (pinfunction "A1_2") (pintype "input"))
      (node (ref "IC35") (pin "18") (pinfunction "Y1_18") (pintype "tri_state"))
      (node (ref "RS08") (pin "33") (pinfunction "33_33") (pintype "passive"))
    )
    (net (code "48") (name "DIO04") (class "Default")
      (node (ref "IC15") (pin "2") (pinfunction "H_2") (pintype "input"))
      (node (ref "IC26") (pin "17") (pinfunction "A4_17") (pintype "input"))
      (node (ref "IC28") (pin "3") (pinfunction "Y4_3") (pintype "tri_state"))
      (node (ref "RS08") (pin "24") (pinfunction "24_24") (pintype "passive"))
    )
    (net (code "49") (name "DIO05") (class "Default")
      (node (ref "IC15") (pin "1") (pinfunction "G_1") (pintype "input"))
      (node (ref "IC26") (pin "15") (pinfunction "A3_15") (pintype "input"))
      (node (ref "IC28") (pin "5") (pinfunction "Y3_5") (pintype "tri_state"))
      (node (ref "RS08") (pin "26") (pinfunction "26_26") (pintype "passive"))
    )
    (net (code "50") (name "DIO06") (class "Default")
      (node (ref "IC15") (pin "13") (pinfunction "F_13") (pintype "input"))
      (node (ref "IC26") (pin "13") (pinfunction "A2_13") (pintype "input"))
      (node (ref "IC28") (pin "7") (pinfunction "Y2_7") (pintype "tri_state"))
      (node (ref "RS08") (pin "28") (pinfunction "28_28") (pintype "passive"))
    )
    (net (code "51") (name "DIO07") (class "Default")
      (node (ref "IC15") (pin "12") (pinfunction "E_12") (pintype "input"))
      (node (ref "IC26") (pin "11") (pinfunction "A1_11") (pintype "input"))
      (node (ref "IC28") (pin "9") (pinfunction "Y1_9") (pintype "tri_state"))
      (node (ref "RS08") (pin "30") (pinfunction "30_30") (pintype "passive"))
    )
    (net (code "52") (name "DIO08") (class "Default")
      (node (ref "IC15") (pin "11") (pinfunction "D_11") (pintype "input"))
      (node (ref "IC26") (pin "8") (pinfunction "A4_8") (pintype "input"))
      (node (ref "IC28") (pin "12") (pinfunction "Y4_12") (pintype "tri_state"))
      (node (ref "RS08") (pin "32") (pinfunction "32_32") (pintype "passive"))
    )
    (net (code "53") (name "DIO09") (class "Default")
      (node (ref "IC15") (pin "10") (pinfunction "C_10") (pintype "input"))
      (node (ref "IC26") (pin "6") (pinfunction "A3_6") (pintype "input"))
      (node (ref "IC28") (pin "14") (pinfunction "Y3_14") (pintype "tri_state"))
      (node (ref "RS08") (pin "29") (pinfunction "29_29") (pintype "passive"))
    )
    (net (code "54") (name "DIO10") (class "Default")
      (node (ref "IC15") (pin "9") (pinfunction "B_9") (pintype "input"))
      (node (ref "IC26") (pin "4") (pinfunction "A2_4") (pintype "input"))
      (node (ref "IC28") (pin "16") (pinfunction "Y2_16") (pintype "tri_state"))
      (node (ref "RS08") (pin "27") (pinfunction "27_27") (pintype "passive"))
    )
    (net (code "55") (name "DIO11") (class "Default")
      (node (ref "IC15") (pin "8") (pinfunction "A_8") (pintype "input"))
      (node (ref "IC26") (pin "2") (pinfunction "A1_2") (pintype "input"))
      (node (ref "IC28") (pin "18") (pinfunction "Y1_18") (pintype "tri_state"))
      (node (ref "RS08") (pin "25") (pinfunction "25_25") (pintype "passive"))
    )
    (net (code "56") (name "DIOEVEN") (class "Default")
      (node (ref "IC13") (pin "13") (pinfunction "F_13") (pintype "input"))
      (node (ref "IC35") (pin "9") (pinfunction "Y1_9") (pintype "tri_state"))
      (node (ref "RS08") (pin "34") (pinfunction "34_34") (pintype "passive"))
    )
    (net (code "57") (name "DMA00") (class "Default")
      (node (ref "DMA0-3") (pin "7") (pinfunction "QD_7") (pintype "output"))
      (node (ref "IC38") (pin "8") (pinfunction "A4_8") (pintype "input"))
      (node (ref "RS08") (pin "16") (pinfunction "16_16") (pintype "passive"))
    )
    (net (code "58") (name "DMA01") (class "Default")
      (node (ref "DMA0-3") (pin "6") (pinfunction "QC_6") (pintype "output"))
      (node (ref "IC38") (pin "6") (pinfunction "A3_6") (pintype "input"))
      (node (ref "RS08") (pin "20") (pinfunction "20_20") (pintype "passive"))
    )
    (net (code "59") (name "DMA02") (class "Default")
      (node (ref "DMA0-3") (pin "2") (pinfunction "QB_2") (pintype "output"))
      (node (ref "IC38") (pin "4") (pinfunction "A2_4") (pintype "input"))
      (node (ref "RS08") (pin "14") (pinfunction "14_14") (pintype "passive"))
    )
    (net (code "60") (name "DMA03") (class "Default")
      (node (ref "DMA0-3") (pin "3") (pinfunction "QA_3") (pintype "output"))
      (node (ref "IC38") (pin "2") (pinfunction "A1_2") (pintype "input"))
      (node (ref "RS08") (pin "12") (pinfunction "12_12") (pintype "passive"))
    )
    (net (code "61") (name "DMA04") (class "Default")
      (node (ref "DMA4-7") (pin "7") (pinfunction "QD_7") (pintype "output"))
      (node (ref "IC31") (pin "8") (pinfunction "A4_8") (pintype "input"))
      (node (ref "RS08") (pin "9") (pinfunction "9_9") (pintype "passive"))
    )
    (net (code "62") (name "DMA05") (class "Default")
      (node (ref "DMA4-7") (pin "6") (pinfunction "QC_6") (pintype "output"))
      (node (ref "IC31") (pin "6") (pinfunction "A3_6") (pintype "input"))
      (node (ref "RS08") (pin "11") (pinfunction "11_11") (pintype "passive"))
    )
    (net (code "63") (name "DMA06") (class "Default")
      (node (ref "DMA4-7") (pin "2") (pinfunction "QB_2") (pintype "output"))
      (node (ref "IC31") (pin "4") (pinfunction "A2_4") (pintype "input"))
      (node (ref "RS08") (pin "13") (pinfunction "13_13") (pintype "passive"))
    )
    (net (code "64") (name "DMA07") (class "Default")
      (node (ref "DMA4-7") (pin "3") (pinfunction "QA_3") (pintype "output"))
      (node (ref "IC31") (pin "2") (pinfunction "A1_2") (pintype "input"))
      (node (ref "RS08") (pin "15") (pinfunction "15_15") (pintype "passive"))
    )
    (net (code "65") (name "DMA08") (class "Default")
      (node (ref "DMA8-11") (pin "7") (pinfunction "QD_7") (pintype "output"))
      (node (ref "IC24") (pin "8") (pinfunction "A4_8") (pintype "input"))
      (node (ref "RS08") (pin "17") (pinfunction "17_17") (pintype "passive"))
    )
    (net (code "66") (name "DMA09") (class "Default")
      (node (ref "DMA8-11") (pin "6") (pinfunction "QC_6") (pintype "output"))
      (node (ref "IC24") (pin "6") (pinfunction "A3_6") (pintype "input"))
      (node (ref "RS08") (pin "19") (pinfunction "19_19") (pintype "passive"))
    )
    (net (code "67") (name "DMA10") (class "Default")
      (node (ref "DMA8-11") (pin "2") (pinfunction "QB_2") (pintype "output"))
      (node (ref "IC24") (pin "4") (pinfunction "A2_4") (pintype "input"))
      (node (ref "RS08") (pin "21") (pinfunction "21_21") (pintype "passive"))
    )
    (net (code "68") (name "DMA11") (class "Default")
      (node (ref "DMA8-11") (pin "3") (pinfunction "QA_3") (pintype "output"))
      (node (ref "IC24") (pin "2") (pinfunction "A1_2") (pintype "input"))
      (node (ref "RS08") (pin "23") (pinfunction "23_23") (pintype "passive"))
    )
    (net (code "69") (name "DONE") (class "Default")
      (node (ref "IC11") (pin "9") (pinfunction "Q_9") (pintype "output"))
      (node (ref "IC40") (pin "2") (pinfunction "I1_2") (pintype "input"))
    )
    (net (code "70") (name "EIE") (class "Default")
      (node (ref "IC37") (pin "2") (pinfunction "A1_2") (pintype "input"))
      (node (ref "IC40") (pin "9") (pinfunction "I0_9") (pintype "input"))
      (node (ref "INTENB") (pin "6") (pinfunction "QC_6") (pintype "output"))
    )
    (net (code "71") (name "ERROR") (class "Default")
      (node (ref "IC12") (pin "6") (pinfunction "O_6") (pintype "output"))
      (node (ref "IC40") (pin "10") (pinfunction "I1_10") (pintype "input"))
      (node (ref "IC7") (pin "2") (pinfunction "A_2") (pintype "input"))
    )
    (net (code "72") (name "F.1") (class "Default")
      (node (ref "FIELD") (pin "3") (pinfunction "QA_3") (pintype "output"))
      (node (ref "IC20") (pin "11") (pinfunction "A1_11") (pintype "input"))
      (node (ref "IC30") (pin "8") (pinfunction "A4_8") (pintype "input"))
    )
    (net (code "73") (name "F.2") (class "Default")
      (node (ref "FIELD") (pin "2") (pinfunction "QB_2") (pintype "output"))
      (node (ref "IC20") (pin "13") (pinfunction "A2_13") (pintype "input"))
      (node (ref "IC30") (pin "11") (pinfunction "A1_11") (pintype "input"))
    )
    (net (code "74") (name "F.3") (class "Default")
      (node (ref "FIELD") (pin "6") (pinfunction "QC_6") (pintype "output"))
      (node (ref "IC20") (pin "15") (pinfunction "A3_15") (pintype "input"))
      (node (ref "IC30") (pin "13") (pinfunction "A2_13") (pintype "input"))
    )
    (net (code "75") (name "GND") (class "Default")
      (node (ref "C1") (pin "2") (pinfunction "2_2") (pintype "passive"))
      (node (ref "C10") (pin "2") (pinfunction "2_2") (pintype "passive"))
      (node (ref "C11") (pin "2") (pinfunction "2_2") (pintype "passive"))
      (node (ref "C12") (pin "2") (pinfunction "2_2") (pintype "passive"))
      (node (ref "C13") (pin "2") (pinfunction "2_2") (pintype "passive"))
      (node (ref "C14") (pin "2") (pinfunction "2_2") (pintype "passive"))
      (node (ref "C15") (pin "2") (pinfunction "2_2") (pintype "passive"))
      (node (ref "C16") (pin "2") (pinfunction "2_2") (pintype "passive"))
      (node (ref "C17") (pin "2") (pinfunction "2_2") (pintype "passive"))
      (node (ref "C18") (pin "2") (pinfunction "2_2") (pintype "passive"))
      (node (ref "C19") (pin "2") (pinfunction "2_2") (pintype "passive"))
      (node (ref "C2") (pin "2") (pinfunction "2_2") (pintype "passive"))
      (node (ref "C20") (pin "2") (pinfunction "2_2") (pintype "passive"))
      (node (ref "C21") (pin "2") (pinfunction "2_2") (pintype "passive"))
      (node (ref "C22") (pin "2") (pinfunction "2_2") (pintype "passive"))
      (node (ref "C23") (pin "2") (pinfunction "2_2") (pintype "passive"))
      (node (ref "C24") (pin "2") (pinfunction "2_2") (pintype "passive"))
      (node (ref "C25") (pin "2") (pinfunction "2_2") (pintype "passive"))
      (node (ref "C26") (pin "2") (pinfunction "2_2") (pintype "passive"))
      (node (ref "C27") (pin "2") (pinfunction "2_2") (pintype "passive"))
      (node (ref "C28") (pin "2") (pinfunction "2_2") (pintype "passive"))
      (node (ref "C29") (pin "2") (pinfunction "2_2") (pintype "passive"))
      (node (ref "C3") (pin "2") (pinfunction "2_2") (pintype "passive"))
      (node (ref "C30") (pin "2") (pinfunction "2_2") (pintype "passive"))
      (node (ref "C31") (pin "2") (pinfunction "2_2") (pintype "passive"))
      (node (ref "C32") (pin "2") (pinfunction "2_2") (pintype "passive"))
      (node (ref "C33") (pin "2") (pinfunction "2_2") (pintype "passive"))
      (node (ref "C34") (pin "2") (pinfunction "2_2") (pintype "passive"))
      (node (ref "C35") (pin "2") (pinfunction "2_2") (pintype "passive"))
      (node (ref "C35L") (pin "1") (pinfunction "1_1") (pintype "passive"))
      (node (ref "C35L") (pin "11") (pinfunction "11_11") (pintype "passive"))
      (node (ref "C35L") (pin "13") (pinfunction "13_13") (pintype "passive"))
      (node (ref "C35L") (pin "15") (pinfunction "15_15") (pintype "passive"))
      (node (ref "C35L") (pin "17") (pinfunction "17_17") (pintype "passive"))
      (node (ref "C35L") (pin "19") (pinfunction "19_19") (pintype "passive"))
      (node (ref "C35L") (pin "21") (pinfunction "21_21") (pintype "passive"))
      (node (ref "C35L") (pin "23") (pinfunction "23_23") (pintype "passive"))
      (node (ref "C35L") (pin "25") (pinfunction "25_25") (pintype "passive"))
      (node (ref "C35L") (pin "27") (pinfunction "27_27") (pintype "passive"))
      (node (ref "C35L") (pin "29") (pinfunction "29_29") (pintype "passive"))
      (node (ref "C35L") (pin "3") (pinfunction "3_3") (pintype "passive"))
      (node (ref "C35L") (pin "31") (pinfunction "31_31") (pintype "passive"))
      (node (ref "C35L") (pin "33") (pinfunction "33_33") (pintype "passive"))
      (node (ref "C35L") (pin "35") (pinfunction "35_35") (pintype "passive"))
      (node (ref "C35L") (pin "37") (pinfunction "37_37") (pintype "passive"))
      (node (ref "C35L") (pin "39") (pinfunction "39_39") (pintype "passive"))
      (node (ref "C35L") (pin "5") (pinfunction "5_5") (pintype "passive"))
      (node (ref "C35L") (pin "7") (pinfunction "7_7") (pintype "passive"))
      (node (ref "C35L") (pin "9") (pinfunction "9_9") (pintype "passive"))
      (node (ref "C36") (pin "2") (pinfunction "2_2") (pintype "passive"))
      (node (ref "C36L") (pin "1") (pinfunction "1_1") (pintype "passive"))
      (node (ref "C36L") (pin "11") (pinfunction "11_11") (pintype "passive"))
      (node (ref "C36L") (pin "13") (pinfunction "13_13") (pintype "passive"))
      (node (ref "C36L") (pin "15") (pinfunction "15_15") (pintype "passive"))
      (node (ref "C36L") (pin "17") (pinfunction "17_17") (pintype "passive"))
      (node (ref "C36L") (pin "19") (pinfunction "19_19") (pintype "passive"))
      (node (ref "C36L") (pin "21") (pinfunction "21_21") (pintype "passive"))
      (node (ref "C36L") (pin "23") (pinfunction "23_23") (pintype "passive"))
      (node (ref "C36L") (pin "25") (pinfunction "25_25") (pintype "passive"))
      (node (ref "C36L") (pin "27") (pinfunction "27_27") (pintype "passive"))
      (node (ref "C36L") (pin "29") (pinfunction "29_29") (pintype "passive"))
      (node (ref "C36L") (pin "3") (pinfunction "3_3") (pintype "passive"))
      (node (ref "C36L") (pin "31") (pinfunction "31_31") (pintype "passive"))
      (node (ref "C36L") (pin "33") (pinfunction "33_33") (pintype "passive"))
      (node (ref "C36L") (pin "35") (pinfunction "35_35") (pintype "passive"))
      (node (ref "C36L") (pin "37") (pinfunction "37_37") (pintype "passive"))
      (node (ref "C36L") (pin "39") (pinfunction "39_39") (pintype "passive"))
      (node (ref "C36L") (pin "5") (pinfunction "5_5") (pintype "passive"))
      (node (ref "C36L") (pin "7") (pinfunction "7_7") (pintype "passive"))
      (node (ref "C36L") (pin "9") (pinfunction "9_9") (pintype "passive"))
      (node (ref "C37") (pin "2") (pinfunction "2_2") (pintype "passive"))
      (node (ref "C38") (pin "2") (pinfunction "2_2") (pintype "passive"))
      (node (ref "C39") (pin "2") (pinfunction "2_2") (pintype "passive"))
      (node (ref "C4") (pin "2") (pinfunction "2_2") (pintype "passive"))
      (node (ref "C40") (pin "2") (pinfunction "2_2") (pintype "passive"))
      (node (ref "C41") (pin "2") (pinfunction "2_2") (pintype "passive"))
      (node (ref "C42") (pin "2") (pinfunction "2_2") (pintype "passive"))
      (node (ref "C43") (pin "2") (pinfunction "2_2") (pintype "passive"))
      (node (ref "C44") (pin "2") (pinfunction "2_2") (pintype "passive"))
      (node (ref "C44X") (pin "2") (pinfunction "2_2") (pintype "passive"))
      (node (ref "C45") (pin "-") (pinfunction "-_-") (pintype "passive"))
      (node (ref "C46") (pin "2") (pinfunction "2_2") (pintype "passive"))
      (node (ref "C5") (pin "2") (pinfunction "2_2") (pintype "passive"))
      (node (ref "C6") (pin "2") (pinfunction "2_2") (pintype "passive"))
      (node (ref "C7") (pin "2") (pinfunction "2_2") (pintype "passive"))
      (node (ref "C8") (pin "2") (pinfunction "2_2") (pintype "passive"))
      (node (ref "C9") (pin "2") (pinfunction "2_2") (pintype "passive"))
      (node (ref "D34L") (pin "1") (pinfunction "1_1") (pintype "passive"))
      (node (ref "D34L") (pin "11") (pinfunction "11_11") (pintype "passive"))
      (node (ref "D34L") (pin "13") (pinfunction "13_13") (pintype "passive"))
      (node (ref "D34L") (pin "15") (pinfunction "15_15") (pintype "passive"))
      (node (ref "D34L") (pin "17") (pinfunction "17_17") (pintype "passive"))
      (node (ref "D34L") (pin "19") (pinfunction "19_19") (pintype "passive"))
      (node (ref "D34L") (pin "21") (pinfunction "21_21") (pintype "passive"))
      (node (ref "D34L") (pin "23") (pinfunction "23_23") (pintype "passive"))
      (node (ref "D34L") (pin "25") (pinfunction "25_25") (pintype "passive"))
      (node (ref "D34L") (pin "27") (pinfunction "27_27") (pintype "passive"))
      (node (ref "D34L") (pin "29") (pinfunction "29_29") (pintype "passive"))
      (node (ref "D34L") (pin "3") (pinfunction "3_3") (pintype "passive"))
      (node (ref "D34L") (pin "31") (pinfunction "31_31") (pintype "passive"))
      (node (ref "D34L") (pin "33") (pinfunction "33_33") (pintype "passive"))
      (node (ref "D34L") (pin "35") (pinfunction "35_35") (pintype "passive"))
      (node (ref "D34L") (pin "37") (pinfunction "37_37") (pintype "passive"))
      (node (ref "D34L") (pin "39") (pinfunction "39_39") (pintype "passive"))
      (node (ref "D34L") (pin "5") (pinfunction "5_5") (pintype "passive"))
      (node (ref "D34L") (pin "7") (pinfunction "7_7") (pintype "passive"))
      (node (ref "D34L") (pin "9") (pinfunction "9_9") (pintype "passive"))
      (node (ref "D35L") (pin "1") (pinfunction "1_1") (pintype "passive"))
      (node (ref "D35L") (pin "11") (pinfunction "11_11") (pintype "passive"))
      (node (ref "D35L") (pin "13") (pinfunction "13_13") (pintype "passive"))
      (node (ref "D35L") (pin "15") (pinfunction "15_15") (pintype "passive"))
      (node (ref "D35L") (pin "17") (pinfunction "17_17") (pintype "passive"))
      (node (ref "D35L") (pin "19") (pinfunction "19_19") (pintype "passive"))
      (node (ref "D35L") (pin "21") (pinfunction "21_21") (pintype "passive"))
      (node (ref "D35L") (pin "23") (pinfunction "23_23") (pintype "passive"))
      (node (ref "D35L") (pin "25") (pinfunction "25_25") (pintype "passive"))
      (node (ref "D35L") (pin "27") (pinfunction "27_27") (pintype "passive"))
      (node (ref "D35L") (pin "29") (pinfunction "29_29") (pintype "passive"))
      (node (ref "D35L") (pin "3") (pinfunction "3_3") (pintype "passive"))
      (node (ref "D35L") (pin "31") (pinfunction "31_31") (pintype "passive"))
      (node (ref "D35L") (pin "33") (pinfunction "33_33") (pintype "passive"))
      (node (ref "D35L") (pin "35") (pinfunction "35_35") (pintype "passive"))
      (node (ref "D35L") (pin "37") (pinfunction "37_37") (pintype "passive"))
      (node (ref "D35L") (pin "39") (pinfunction "39_39") (pintype "passive"))
      (node (ref "D35L") (pin "5") (pinfunction "5_5") (pintype "passive"))
      (node (ref "D35L") (pin "7") (pinfunction "7_7") (pintype "passive"))
      (node (ref "D35L") (pin "9") (pinfunction "9_9") (pintype "passive"))
      (node (ref "D36L") (pin "1") (pinfunction "1_1") (pintype "passive"))
      (node (ref "D36L") (pin "11") (pinfunction "11_11") (pintype "passive"))
      (node (ref "D36L") (pin "13") (pinfunction "13_13") (pintype "passive"))
      (node (ref "D36L") (pin "15") (pinfunction "15_15") (pintype "passive"))
      (node (ref "D36L") (pin "17") (pinfunction "17_17") (pintype "passive"))
      (node (ref "D36L") (pin "19") (pinfunction "19_19") (pintype "passive"))
      (node (ref "D36L") (pin "21") (pinfunction "21_21") (pintype "passive"))
      (node (ref "D36L") (pin "23") (pinfunction "23_23") (pintype "passive"))
      (node (ref "D36L") (pin "25") (pinfunction "25_25") (pintype "passive"))
      (node (ref "D36L") (pin "27") (pinfunction "27_27") (pintype "passive"))
      (node (ref "D36L") (pin "29") (pinfunction "29_29") (pintype "passive"))
      (node (ref "D36L") (pin "3") (pinfunction "3_3") (pintype "passive"))
      (node (ref "D36L") (pin "31") (pinfunction "31_31") (pintype "passive"))
      (node (ref "D36L") (pin "33") (pinfunction "33_33") (pintype "passive"))
      (node (ref "D36L") (pin "35") (pinfunction "35_35") (pintype "passive"))
      (node (ref "D36L") (pin "37") (pinfunction "37_37") (pintype "passive"))
      (node (ref "D36L") (pin "39") (pinfunction "39_39") (pintype "passive"))
      (node (ref "D36L") (pin "5") (pinfunction "5_5") (pintype "passive"))
      (node (ref "D36L") (pin "7") (pinfunction "7_7") (pintype "passive"))
      (node (ref "D36L") (pin "9") (pinfunction "9_9") (pintype "passive"))
      (node (ref "DAR4-7") (pin "4") (pinfunction "DN_4") (pintype "input"))
      (node (ref "DAR8-11") (pin "4") (pinfunction "DN_4") (pintype "input"))
      (node (ref "DMA0-3") (pin "4") (pinfunction "DN_4") (pintype "input"))
      (node (ref "DMA4-7") (pin "4") (pinfunction "DN_4") (pintype "input"))
      (node (ref "DMA8-11") (pin "4") (pinfunction "DN_4") (pintype "input"))
      (node (ref "FIELD") (pin "4") (pinfunction "DN_4") (pintype "input"))
      (node (ref "FIELD") (pin "5") (pinfunction "UP_5") (pintype "input"))
      (node (ref "FIELD") (pin "9") (pinfunction "D_9") (pintype "input"))
      (node (ref "IC1") (pin "7") (pinfunction "G_7") (pintype "input"))
      (node (ref "IC10") (pin "12") (pinfunction "D_12") (pintype "input"))
      (node (ref "IC10") (pin "2") (pinfunction "D_2") (pintype "input"))
      (node (ref "IC13") (pin "1") (pinfunction "G_1") (pintype "input"))
      (node (ref "IC13") (pin "2") (pinfunction "H_2") (pintype "input"))
      (node (ref "IC14") (pin "1") (pinfunction "G_1") (pintype "input"))
      (node (ref "IC14") (pin "13") (pinfunction "F_13") (pintype "input"))
      (node (ref "IC14") (pin "2") (pinfunction "H_2") (pintype "input"))
      (node (ref "IC14") (pin "4") (pinfunction "OI_4") (pintype "input"))
      (node (ref "IC15") (pin "4") (pinfunction "OI_4") (pintype "input"))
      (node (ref "IC16") (pin "1") (pinfunction "G_1") (pintype "input"))
      (node (ref "IC16") (pin "15") (pinfunction "G_15") (pintype "input"))
      (node (ref "IC17") (pin "1") (pinfunction "G_1") (pintype "input"))
      (node (ref "IC17") (pin "15") (pinfunction "G_15") (pintype "input"))
      (node (ref "IC2") (pin "7") (pinfunction "G_7") (pintype "input"))
      (node (ref "IC20") (pin "17") (pinfunction "A4_17") (pintype "input"))
      (node (ref "IC23") (pin "2") (pinfunction "D_2") (pintype "input"))
      (node (ref "IC25") (pin "5") (pinfunction "G2B_5") (pintype "input"))
      (node (ref "IC29") (pin "5") (pinfunction "G2B_5") (pintype "input"))
      (node (ref "IC3") (pin "7") (pinfunction "G_7") (pintype "input"))
      (node (ref "IC30") (pin "6") (pinfunction "A3_6") (pintype "input"))
      (node (ref "IC32") (pin "5") (pinfunction "G2B_5") (pintype "input"))
      (node (ref "IC35") (pin "13") (pinfunction "A2_13") (pintype "input"))
      (node (ref "IC35") (pin "15") (pinfunction "A3_15") (pintype "input"))
      (node (ref "IC35") (pin "17") (pinfunction "A4_17") (pintype "input"))
      (node (ref "IC36") (pin "4") (pinfunction "G2A_4") (pintype "input"))
      (node (ref "IC36") (pin "5") (pinfunction "G2B_5") (pintype "input"))
      (node (ref "IC37") (pin "6") (pinfunction "A3_6") (pintype "input"))
      (node (ref "IC38") (pin "11") (pinfunction "A1_11") (pintype "input"))
      (node (ref "IC38") (pin "13") (pinfunction "A2_13") (pintype "input"))
      (node (ref "IC38") (pin "15") (pinfunction "A3_15") (pintype "input"))
      (node (ref "IC38") (pin "17") (pinfunction "A4_17") (pintype "input"))
      (node (ref "IC4") (pin "7") (pinfunction "G_7") (pintype "input"))
      (node (ref "IC7") (pin "1") (pinfunction "G_1") (pintype "input"))
      (node (ref "IC7") (pin "15") (pinfunction "G_15") (pintype "input"))
      (node (ref "IC8") (pin "1") (pinfunction "GND_1") (pintype "power_in"))
      (node (ref "IC9") (pin "12") (pinfunction "D_12") (pintype "input"))
      (node (ref "IC9") (pin "2") (pinfunction "D_2") (pintype "input"))
      (node (ref "INTENB") (pin "4") (pinfunction "DN_4") (pintype "input"))
      (node (ref "INTENB") (pin "5") (pinfunction "UP_5") (pintype "input"))
      (node (ref "INTENB") (pin "9") (pinfunction "D_9") (pintype "input"))
      (node (ref "J10") (pin "2") (pinfunction "2_2") (pintype "passive"))
      (node (ref "J11") (pin "2") (pinfunction "2_2") (pintype "passive"))
      (node (ref "J12") (pin "2") (pinfunction "2_2") (pintype "passive"))
      (node (ref "J13") (pin "2") (pinfunction "2_2") (pintype "passive"))
      (node (ref "J14") (pin "2") (pinfunction "2_2") (pintype "passive"))
      (node (ref "J2") (pin "2") (pinfunction "2_2") (pintype "passive"))
      (node (ref "J6") (pin "2") (pinfunction "2_2") (pintype "passive"))
      (node (ref "J8") (pin "2") (pinfunction "2_2") (pintype "passive"))
      (node (ref "J9") (pin "2") (pinfunction "2_2") (pintype "passive"))
      (node (ref "RS08") (pin "31") (pinfunction "31_31") (pintype "passive"))
      (node (ref "RS08") (pin "39") (pinfunction "39_39") (pintype "passive"))
    )
    (net (code "76") (name "NXD") (class "Default")
      (node (ref "IC23") (pin "5") (pinfunction "Q_5") (pintype "output"))
      (node (ref "IC30") (pin "4") (pinfunction "A2_4") (pintype "input"))
    )
    (net (code "77") (name "Net-(DAR4-7A-CLR)") (class "Default")
      (node (ref "DAR4-7") (pin "14") (pinfunction "CLR_14") (pintype "input"))
      (node (ref "DAR8-11") (pin "14") (pinfunction "CLR_14") (pintype "input"))
      (node (ref "IC18") (pin "8") (pinfunction "O_8") (pintype "output"))
    )
    (net (code "78") (name "Net-(DAR4-7A-UP)") (class "Default")
      (node (ref "DAR4-7") (pin "5") (pinfunction "UP_5") (pintype "input"))
      (node (ref "DAR8-11") (pin "12") (pinfunction "CO_12") (pintype "output"))
    )
    (net (code "79") (name "Net-(DAR8-11A-UP)") (class "Default")
      (node (ref "DAR8-11") (pin "5") (pinfunction "UP_5") (pintype "input"))
      (node (ref "DMA0-3") (pin "12") (pinfunction "CO_12") (pintype "output"))
    )
    (net (code "80") (name "Net-(DMA0-3A-CLR)") (class "Default")
      (node (ref "DMA0-3") (pin "14") (pinfunction "CLR_14") (pintype "input"))
      (node (ref "DMA4-7") (pin "14") (pinfunction "CLR_14") (pintype "input"))
      (node (ref "DMA8-11") (pin "14") (pinfunction "CLR_14") (pintype "input"))
      (node (ref "IC18") (pin "6") (pinfunction "O_6") (pintype "output"))
    )
    (net (code "81") (name "Net-(DMA0-3A-UP)") (class "Default")
      (node (ref "DMA0-3") (pin "5") (pinfunction "UP_5") (pintype "input"))
      (node (ref "DMA4-7") (pin "12") (pinfunction "CO_12") (pintype "output"))
    )
    (net (code "82") (name "Net-(DMA4-7A-UP)") (class "Default")
      (node (ref "DMA4-7") (pin "5") (pinfunction "UP_5") (pintype "input"))
      (node (ref "DMA8-11") (pin "12") (pinfunction "CO_12") (pintype "output"))
    )
    (net (code "83") (name "Net-(IC1A-D0)") (class "Default")
      (node (ref "IC1") (pin "4") (pinfunction "D0_4") (pintype "input"))
      (node (ref "SW1") (pin "16") (pinfunction "16_16") (pintype "passive"))
    )
    (net (code "84") (name "Net-(IC1A-D1)") (class "Default")
      (node (ref "IC1") (pin "3") (pinfunction "D1_3") (pintype "input"))
      (node (ref "SW1") (pin "15") (pinfunction "15_15") (pintype "passive"))
    )
    (net (code "85") (name "Net-(IC1A-D2)") (class "Default")
      (node (ref "IC1") (pin "2") (pinfunction "D2_2") (pintype "input"))
      (node (ref "SW1") (pin "14") (pinfunction "14_14") (pintype "passive"))
    )
    (net (code "86") (name "Net-(IC1A-D3)") (class "Default")
      (node (ref "IC1") (pin "1") (pinfunction "D3_1") (pintype "input"))
      (node (ref "SW1") (pin "13") (pinfunction "13_13") (pintype "passive"))
    )
    (net (code "87") (name "Net-(IC1A-D4)") (class "Default")
      (node (ref "IC1") (pin "15") (pinfunction "D4_15") (pintype "input"))
      (node (ref "SW1") (pin "12") (pinfunction "12_12") (pintype "passive"))
    )
    (net (code "88") (name "Net-(IC1A-D5)") (class "Default")
      (node (ref "IC1") (pin "14") (pinfunction "D5_14") (pintype "input"))
      (node (ref "SW1") (pin "11") (pinfunction "11_11") (pintype "passive"))
    )
    (net (code "89") (name "Net-(IC1A-D6)") (class "Default")
      (node (ref "IC1") (pin "13") (pinfunction "D6_13") (pintype "input"))
      (node (ref "SW1") (pin "10") (pinfunction "10_10") (pintype "passive"))
    )
    (net (code "90") (name "Net-(IC1A-D7)") (class "Default")
      (node (ref "IC1") (pin "12") (pinfunction "D7_12") (pintype "input"))
      (node (ref "SW1") (pin "9") (pinfunction "9_9") (pintype "passive"))
    )
    (net (code "91") (name "Net-(IC1A-Y)") (class "Default")
      (node (ref "IC1") (pin "5") (pinfunction "Y_5") (pintype "output"))
      (node (ref "IC5") (pin "1") (pinfunction "I0_1") (pintype "input"))
    )
    (net (code "92") (name "Net-(IC2A-D0)") (class "Default")
      (node (ref "IC2") (pin "4") (pinfunction "D0_4") (pintype "input"))
      (node (ref "SW2") (pin "16") (pinfunction "16_16") (pintype "passive"))
    )
    (net (code "93") (name "Net-(IC2A-D1)") (class "Default")
      (node (ref "IC2") (pin "3") (pinfunction "D1_3") (pintype "input"))
      (node (ref "SW2") (pin "15") (pinfunction "15_15") (pintype "passive"))
    )
    (net (code "94") (name "Net-(IC2A-D2)") (class "Default")
      (node (ref "IC2") (pin "2") (pinfunction "D2_2") (pintype "input"))
      (node (ref "SW2") (pin "14") (pinfunction "14_14") (pintype "passive"))
    )
    (net (code "95") (name "Net-(IC2A-D3)") (class "Default")
      (node (ref "IC2") (pin "1") (pinfunction "D3_1") (pintype "input"))
      (node (ref "SW2") (pin "13") (pinfunction "13_13") (pintype "passive"))
    )
    (net (code "96") (name "Net-(IC2A-D4)") (class "Default")
      (node (ref "IC2") (pin "15") (pinfunction "D4_15") (pintype "input"))
      (node (ref "SW2") (pin "12") (pinfunction "12_12") (pintype "passive"))
    )
    (net (code "97") (name "Net-(IC2A-D5)") (class "Default")
      (node (ref "IC2") (pin "14") (pinfunction "D5_14") (pintype "input"))
      (node (ref "SW2") (pin "11") (pinfunction "11_11") (pintype "passive"))
    )
    (net (code "98") (name "Net-(IC2A-D6)") (class "Default")
      (node (ref "IC2") (pin "13") (pinfunction "D6_13") (pintype "input"))
      (node (ref "SW2") (pin "10") (pinfunction "10_10") (pintype "passive"))
    )
    (net (code "99") (name "Net-(IC2A-D7)") (class "Default")
      (node (ref "IC2") (pin "12") (pinfunction "D7_12") (pintype "input"))
      (node (ref "SW2") (pin "9") (pinfunction "9_9") (pintype "passive"))
    )
    (net (code "100") (name "Net-(IC2A-Y)") (class "Default")
      (node (ref "IC2") (pin "5") (pinfunction "Y_5") (pintype "output"))
      (node (ref "IC5") (pin "2") (pinfunction "I1_2") (pintype "input"))
    )
    (net (code "101") (name "Net-(IC3A-D0)") (class "Default")
      (node (ref "IC3") (pin "4") (pinfunction "D0_4") (pintype "input"))
      (node (ref "SW3") (pin "16") (pinfunction "16_16") (pintype "passive"))
    )
    (net (code "102") (name "Net-(IC3A-D1)") (class "Default")
      (node (ref "IC3") (pin "3") (pinfunction "D1_3") (pintype "input"))
      (node (ref "SW3") (pin "15") (pinfunction "15_15") (pintype "passive"))
    )
    (net (code "103") (name "Net-(IC3A-D2)") (class "Default")
      (node (ref "IC3") (pin "2") (pinfunction "D2_2") (pintype "input"))
      (node (ref "SW3") (pin "14") (pinfunction "14_14") (pintype "passive"))
    )
    (net (code "104") (name "Net-(IC3A-D3)") (class "Default")
      (node (ref "IC3") (pin "1") (pinfunction "D3_1") (pintype "input"))
      (node (ref "SW3") (pin "13") (pinfunction "13_13") (pintype "passive"))
    )
    (net (code "105") (name "Net-(IC3A-D4)") (class "Default")
      (node (ref "IC3") (pin "15") (pinfunction "D4_15") (pintype "input"))
      (node (ref "SW3") (pin "12") (pinfunction "12_12") (pintype "passive"))
    )
    (net (code "106") (name "Net-(IC3A-D5)") (class "Default")
      (node (ref "IC3") (pin "14") (pinfunction "D5_14") (pintype "input"))
      (node (ref "SW3") (pin "11") (pinfunction "11_11") (pintype "passive"))
    )
    (net (code "107") (name "Net-(IC3A-D6)") (class "Default")
      (node (ref "IC3") (pin "13") (pinfunction "D6_13") (pintype "input"))
      (node (ref "SW3") (pin "10") (pinfunction "10_10") (pintype "passive"))
    )
    (net (code "108") (name "Net-(IC3A-D7)") (class "Default")
      (node (ref "IC3") (pin "12") (pinfunction "D7_12") (pintype "input"))
      (node (ref "SW3") (pin "9") (pinfunction "9_9") (pintype "passive"))
    )
    (net (code "109") (name "Net-(IC3A-Y)") (class "Default")
      (node (ref "IC3") (pin "5") (pinfunction "Y_5") (pintype "output"))
      (node (ref "IC5") (pin "4") (pinfunction "I2_4") (pintype "input"))
    )
    (net (code "110") (name "Net-(IC4A-D0)") (class "Default")
      (node (ref "IC4") (pin "4") (pinfunction "D0_4") (pintype "input"))
      (node (ref "SW4") (pin "16") (pinfunction "16_16") (pintype "passive"))
    )
    (net (code "111") (name "Net-(IC4A-D1)") (class "Default")
      (node (ref "IC4") (pin "3") (pinfunction "D1_3") (pintype "input"))
      (node (ref "SW4") (pin "15") (pinfunction "15_15") (pintype "passive"))
    )
    (net (code "112") (name "Net-(IC4A-D2)") (class "Default")
      (node (ref "IC4") (pin "2") (pinfunction "D2_2") (pintype "input"))
      (node (ref "SW4") (pin "14") (pinfunction "14_14") (pintype "passive"))
    )
    (net (code "113") (name "Net-(IC4A-D3)") (class "Default")
      (node (ref "IC4") (pin "1") (pinfunction "D3_1") (pintype "input"))
      (node (ref "SW4") (pin "13") (pinfunction "13_13") (pintype "passive"))
    )
    (net (code "114") (name "Net-(IC4A-D4)") (class "Default")
      (node (ref "IC4") (pin "15") (pinfunction "D4_15") (pintype "input"))
      (node (ref "SW4") (pin "12") (pinfunction "12_12") (pintype "passive"))
    )
    (net (code "115") (name "Net-(IC4A-D5)") (class "Default")
      (node (ref "IC4") (pin "14") (pinfunction "D5_14") (pintype "input"))
      (node (ref "SW4") (pin "11") (pinfunction "11_11") (pintype "passive"))
    )
    (net (code "116") (name "Net-(IC4A-D6)") (class "Default")
      (node (ref "IC4") (pin "13") (pinfunction "D6_13") (pintype "input"))
      (node (ref "SW4") (pin "10") (pinfunction "10_10") (pintype "passive"))
    )
    (net (code "117") (name "Net-(IC4A-D7)") (class "Default")
      (node (ref "IC4") (pin "12") (pinfunction "D7_12") (pintype "input"))
      (node (ref "SW4") (pin "9") (pinfunction "9_9") (pintype "passive"))
    )
    (net (code "118") (name "Net-(IC4A-Y)") (class "Default")
      (node (ref "IC4") (pin "5") (pinfunction "Y_5") (pintype "output"))
      (node (ref "IC5") (pin "5") (pinfunction "I3_5") (pintype "input"))
    )
    (net (code "119") (name "Net-(IC8-CV)") (class "Default")
      (node (ref "C43X") (pin "2") (pinfunction "2_2") (pintype "passive"))
      (node (ref "IC8") (pin "5") (pinfunction "CV_5") (pintype "input"))
    )
    (net (code "120") (name "Net-(IC8-DIS)") (class "Default")
      (node (ref "IC8") (pin "7") (pinfunction "DIS_7") (pintype "input"))
      (node (ref "RA") (pin "2") (pinfunction "2_2") (pintype "passive"))
      (node (ref "RB") (pin "1") (pinfunction "1_1") (pintype "passive"))
    )
    (net (code "121") (name "Net-(IC8-THR)") (class "Default")
      (node (ref "C44X") (pin "1") (pinfunction "1_1") (pintype "passive"))
      (node (ref "IC8") (pin "2") (pinfunction "TR_2") (pintype "input"))
      (node (ref "IC8") (pin "6") (pinfunction "THR_6") (pintype "input"))
      (node (ref "RB") (pin "2") (pinfunction "2_2") (pintype "passive"))
    )
    (net (code "122") (name "Net-(IC10B-PRE)") (class "Default")
      (node (ref "IC10") (pin "10") (pinfunction "PRE_10") (pintype "input"))
      (node (ref "IC18") (pin "11") (pinfunction "O_11") (pintype "output"))
    )
    (net (code "123") (name "Net-(IC10B-~{Q})") (class "Default")
      (node (ref "IC10") (pin "8") (pinfunction "~{Q}_8") (pintype "output"))
      (node (ref "IC11") (pin "11") (pinfunction "CLK_11") (pintype "input"))
    )
    (net (code "124") (name "Net-(IC12A-I0)") (class "Default")
      (node (ref "IC12") (pin "1") (pinfunction "I0_1") (pintype "input"))
      (node (ref "IC12") (pin "2") (pinfunction "I1_2") (pintype "input"))
      (node (ref "IC8") (pin "3") (pinfunction "Q_3") (pintype "output"))
      (node (ref "RL") (pin "2") (pinfunction "2_2") (pintype "passive"))
    )
    (net (code "125") (name "Net-(IC12B-I1)") (class "Default")
      (node (ref "IC12") (pin "5") (pinfunction "I1_5") (pintype "input"))
      (node (ref "IC12") (pin "8") (pinfunction "O_8") (pintype "output"))
    )
    (net (code "126") (name "Net-(IC12C-I0)") (class "Default")
      (node (ref "IC12") (pin "10") (pinfunction "I1_10") (pintype "input"))
      (node (ref "IC12") (pin "11") (pinfunction "O_11") (pintype "output"))
      (node (ref "IC12") (pin "9") (pinfunction "I0_9") (pintype "input"))
    )
    (net (code "127") (name "Net-(IC13A-A)") (class "Default")
      (node (ref "IC13") (pin "8") (pinfunction "A_8") (pintype "input"))
      (node (ref "IC14") (pin "8") (pinfunction "A_8") (pintype "input"))
      (node (ref "IC15") (pin "6") (pinfunction "ODD_6") (pintype "output"))
    )
    (net (code "128") (name "Net-(IC16B-Y1)") (class "Default")
      (node (ref "IC16") (pin "11") (pinfunction "Y1_11") (pintype "output"))
      (node (ref "IC22") (pin "1") (pinfunction "I_1") (pintype "input"))
    )
    (net (code "129") (name "Net-(IC17A-Y0)") (class "Default")
      (node (ref "IC17") (pin "4") (pinfunction "Y0_4") (pintype "output"))
      (node (ref "IC22") (pin "11") (pinfunction "I_11") (pintype "input"))
    )
    (net (code "130") (name "Net-(IC19A-I)") (class "Default")
      (node (ref "IC19") (pin "1") (pinfunction "I_1") (pintype "input"))
      (node (ref "IC7") (pin "5") (pinfunction "Y1_5") (pintype "output"))
    )
    (net (code "131") (name "Net-(IC19E-I)") (class "Default")
      (node (ref "IC19") (pin "11") (pinfunction "I_11") (pintype "input"))
      (node (ref "IC7") (pin "12") (pinfunction "Y0_12") (pintype "output"))
    )
    (net (code "132") (name "Net-(IC33A-Y0)") (class "Default")
      (node (ref "IC33") (pin "4") (pinfunction "Y0_4") (pintype "output"))
      (node (ref "SW1") (pin "1") (pinfunction "1_1") (pintype "passive"))
      (node (ref "SW1") (pin "2") (pinfunction "2_2") (pintype "passive"))
      (node (ref "SW1") (pin "3") (pinfunction "3_3") (pintype "passive"))
      (node (ref "SW1") (pin "4") (pinfunction "4_4") (pintype "passive"))
      (node (ref "SW1") (pin "5") (pinfunction "5_5") (pintype "passive"))
      (node (ref "SW1") (pin "6") (pinfunction "6_6") (pintype "passive"))
      (node (ref "SW1") (pin "7") (pinfunction "7_7") (pintype "passive"))
      (node (ref "SW1") (pin "8") (pinfunction "8_8") (pintype "passive"))
    )
    (net (code "133") (name "Net-(IC33A-Y1)") (class "Default")
      (node (ref "IC33") (pin "5") (pinfunction "Y1_5") (pintype "output"))
      (node (ref "SW2") (pin "1") (pinfunction "1_1") (pintype "passive"))
      (node (ref "SW2") (pin "2") (pinfunction "2_2") (pintype "passive"))
      (node (ref "SW2") (pin "3") (pinfunction "3_3") (pintype "passive"))
      (node (ref "SW2") (pin "4") (pinfunction "4_4") (pintype "passive"))
      (node (ref "SW2") (pin "5") (pinfunction "5_5") (pintype "passive"))
      (node (ref "SW2") (pin "6") (pinfunction "6_6") (pintype "passive"))
      (node (ref "SW2") (pin "7") (pinfunction "7_7") (pintype "passive"))
      (node (ref "SW2") (pin "8") (pinfunction "8_8") (pintype "passive"))
    )
    (net (code "134") (name "Net-(IC33A-Y2)") (class "Default")
      (node (ref "IC33") (pin "6") (pinfunction "Y2_6") (pintype "output"))
      (node (ref "SW3") (pin "1") (pinfunction "1_1") (pintype "passive"))
      (node (ref "SW3") (pin "2") (pinfunction "2_2") (pintype "passive"))
      (node (ref "SW3") (pin "3") (pinfunction "3_3") (pintype "passive"))
      (node (ref "SW3") (pin "4") (pinfunction "4_4") (pintype "passive"))
      (node (ref "SW3") (pin "5") (pinfunction "5_5") (pintype "passive"))
      (node (ref "SW3") (pin "6") (pinfunction "6_6") (pintype "passive"))
      (node (ref "SW3") (pin "7") (pinfunction "7_7") (pintype "passive"))
      (node (ref "SW3") (pin "8") (pinfunction "8_8") (pintype "passive"))
    )
    (net (code "135") (name "Net-(IC33A-Y3)") (class "Default")
      (node (ref "IC33") (pin "7") (pinfunction "Y3_7") (pintype "output"))
      (node (ref "SW4") (pin "1") (pinfunction "1_1") (pintype "passive"))
      (node (ref "SW4") (pin "2") (pinfunction "2_2") (pintype "passive"))
      (node (ref "SW4") (pin "3") (pinfunction "3_3") (pintype "passive"))
      (node (ref "SW4") (pin "4") (pinfunction "4_4") (pintype "passive"))
      (node (ref "SW4") (pin "5") (pinfunction "5_5") (pintype "passive"))
      (node (ref "SW4") (pin "6") (pinfunction "6_6") (pintype "passive"))
      (node (ref "SW4") (pin "7") (pinfunction "7_7") (pintype "passive"))
      (node (ref "SW4") (pin "8") (pinfunction "8_8") (pintype "passive"))
    )
    (net (code "136") (name "Net-(IC36A-Y0)") (class "Default")
      (node (ref "IC36") (pin "15") (pinfunction "Y0_15") (pintype "output"))
      (node (ref "PAD2") (pin "1") (pinfunction "P_1") (pintype "passive"))
    )
    (net (code "137") (name "Net-(IC36A-Y1)") (class "Default")
      (node (ref "IC36") (pin "14") (pinfunction "Y1_14") (pintype "output"))
      (node (ref "PAD3") (pin "1") (pinfunction "P_1") (pintype "passive"))
    )
    (net (code "138") (name "Net-(IC36A-Y2)") (class "Default")
      (node (ref "IC36") (pin "13") (pinfunction "Y2_13") (pintype "output"))
      (node (ref "PAD4") (pin "1") (pinfunction "P_1") (pintype "passive"))
    )
    (net (code "139") (name "Net-(IC36A-Y3)") (class "Default")
      (node (ref "IC36") (pin "12") (pinfunction "Y3_12") (pintype "output"))
      (node (ref "PAD5") (pin "1") (pinfunction "P_1") (pintype "passive"))
    )
    (net (code "140") (name "Net-(IC36A-Y4)") (class "Default")
      (node (ref "IC36") (pin "11") (pinfunction "Y4_11") (pintype "output"))
      (node (ref "PAD6") (pin "1") (pinfunction "P_1") (pintype "passive"))
    )
    (net (code "141") (name "Net-(IC36A-Y5)") (class "Default")
      (node (ref "IC36") (pin "10") (pinfunction "Y5_10") (pintype "output"))
      (node (ref "PAD7") (pin "1") (pinfunction "P_1") (pintype "passive"))
    )
    (net (code "142") (name "Net-(IC36A-Y6)") (class "Default")
      (node (ref "IC36") (pin "9") (pinfunction "Y6_9") (pintype "output"))
      (node (ref "PAD8") (pin "1") (pinfunction "P_1") (pintype "passive"))
    )
    (net (code "143") (name "Net-(IC36A-Y7)") (class "Default")
      (node (ref "IC36") (pin "7") (pinfunction "Y7_7") (pintype "output"))
      (node (ref "PAD9") (pin "1") (pinfunction "P_1") (pintype "passive"))
    )
    (net (code "144") (name "PBIT") (class "Default")
      (node (ref "IC14") (pin "6") (pinfunction "ODD_6") (pintype "output"))
      (node (ref "IC35") (pin "11") (pinfunction "A1_11") (pintype "input"))
    )
    (net (code "145") (name "PCA") (class "Default")
      (node (ref "IC12") (pin "3") (pinfunction "O_3") (pintype "output"))
      (node (ref "IC37") (pin "8") (pinfunction "A4_8") (pintype "input"))
      (node (ref "IC40") (pin "5") (pinfunction "I1_5") (pintype "input"))
    )
    (net (code "146") (name "PER") (class "Default")
      (node (ref "IC30") (pin "2") (pinfunction "A1_2") (pintype "input"))
      (node (ref "IC9") (pin "9") (pinfunction "Q_9") (pintype "output"))
    )
    (net (code "147") (name "PIE") (class "Default")
      (node (ref "IC30") (pin "17") (pinfunction "A4_17") (pintype "input"))
      (node (ref "IC40") (pin "4") (pinfunction "I0_4") (pintype "input"))
      (node (ref "INTENB") (pin "2") (pinfunction "QB_2") (pintype "output"))
    )
    (net (code "148") (name "PROTECT") (class "Default")
      (node (ref "IC5") (pin "6") (pinfunction "O_6") (pintype "output"))
      (node (ref "IC6") (pin "3") (pinfunction "B_3") (pintype "input"))
    )
    (net (code "149") (name "VCC") (class "Default")
      (node (ref "C1") (pin "1") (pinfunction "1_1") (pintype "passive"))
      (node (ref "C10") (pin "1") (pinfunction "1_1") (pintype "passive"))
      (node (ref "C11") (pin "1") (pinfunction "1_1") (pintype "passive"))
      (node (ref "C12") (pin "1") (pinfunction "1_1") (pintype "passive"))
      (node (ref "C13") (pin "1") (pinfunction "1_1") (pintype "passive"))
      (node (ref "C14") (pin "1") (pinfunction "1_1") (pintype "passive"))
      (node (ref "C15") (pin "1") (pinfunction "1_1") (pintype "passive"))
      (node (ref "C16") (pin "1") (pinfunction "1_1") (pintype "passive"))
      (node (ref "C17") (pin "1") (pinfunction "1_1") (pintype "passive"))
      (node (ref "C18") (pin "1") (pinfunction "1_1") (pintype "passive"))
      (node (ref "C19") (pin "1") (pinfunction "1_1") (pintype "passive"))
      (node (ref "C2") (pin "1") (pinfunction "1_1") (pintype "passive"))
      (node (ref "C20") (pin "1") (pinfunction "1_1") (pintype "passive"))
      (node (ref "C21") (pin "1") (pinfunction "1_1") (pintype "passive"))
      (node (ref "C22") (pin "1") (pinfunction "1_1") (pintype "passive"))
      (node (ref "C23") (pin "1") (pinfunction "1_1") (pintype "passive"))
      (node (ref "C24") (pin "1") (pinfunction "1_1") (pintype "passive"))
      (node (ref "C25") (pin "1") (pinfunction "1_1") (pintype "passive"))
      (node (ref "C26") (pin "1") (pinfunction "1_1") (pintype "passive"))
      (node (ref "C27") (pin "1") (pinfunction "1_1") (pintype "passive"))
      (node (ref "C28") (pin "1") (pinfunction "1_1") (pintype "passive"))
      (node (ref "C29") (pin "1") (pinfunction "1_1") (pintype "passive"))
      (node (ref "C3") (pin "1") (pinfunction "1_1") (pintype "passive"))
      (node (ref "C30") (pin "1") (pinfunction "1_1") (pintype "passive"))
      (node (ref "C31") (pin "1") (pinfunction "1_1") (pintype "passive"))
      (node (ref "C32") (pin "1") (pinfunction "1_1") (pintype "passive"))
      (node (ref "C33") (pin "1") (pinfunction "1_1") (pintype "passive"))
      (node (ref "C34") (pin "1") (pinfunction "1_1") (pintype "passive"))
      (node (ref "C35") (pin "1") (pinfunction "1_1") (pintype "passive"))
      (node (ref "C36") (pin "1") (pinfunction "1_1") (pintype "passive"))
      (node (ref "C37") (pin "1") (pinfunction "1_1") (pintype "passive"))
      (node (ref "C38") (pin "1") (pinfunction "1_1") (pintype "passive"))
      (node (ref "C39") (pin "1") (pinfunction "1_1") (pintype "passive"))
      (node (ref "C4") (pin "1") (pinfunction "1_1") (pintype "passive"))
      (node (ref "C40") (pin "1") (pinfunction "1_1") (pintype "passive"))
      (node (ref "C41") (pin "1") (pinfunction "1_1") (pintype "passive"))
      (node (ref "C42") (pin "1") (pinfunction "1_1") (pintype "passive"))
      (node (ref "C43") (pin "1") (pinfunction "1_1") (pintype "passive"))
      (node (ref "C43X") (pin "1") (pinfunction "1_1") (pintype "passive"))
      (node (ref "C44") (pin "1") (pinfunction "1_1") (pintype "passive"))
      (node (ref "C45") (pin "+") (pinfunction "+_+") (pintype "passive"))
      (node (ref "C46") (pin "1") (pinfunction "1_1") (pintype "passive"))
      (node (ref "C5") (pin "1") (pinfunction "1_1") (pintype "passive"))
      (node (ref "C6") (pin "1") (pinfunction "1_1") (pintype "passive"))
      (node (ref "C7") (pin "1") (pinfunction "1_1") (pintype "passive"))
      (node (ref "C8") (pin "1") (pinfunction "1_1") (pintype "passive"))
      (node (ref "C9") (pin "1") (pinfunction "1_1") (pintype "passive"))
      (node (ref "IC11") (pin "10") (pinfunction "PRE_10") (pintype "input"))
      (node (ref "IC11") (pin "4") (pinfunction "PRE_4") (pintype "input"))
      (node (ref "IC13") (pin "3") (pinfunction "EI_3") (pintype "input"))
      (node (ref "IC14") (pin "3") (pinfunction "EI_3") (pintype "input"))
      (node (ref "IC15") (pin "3") (pinfunction "EI_3") (pintype "input"))
      (node (ref "IC36") (pin "6") (pinfunction "G1_6") (pintype "input"))
      (node (ref "IC8") (pin "4") (pinfunction "R_4") (pintype "input"))
      (node (ref "IC8") (pin "8") (pinfunction "V+_8") (pintype "power_in"))
      (node (ref "J3") (pin "2") (pinfunction "2_2") (pintype "passive"))
      (node (ref "J4") (pin "2") (pinfunction "2_2") (pintype "passive"))
      (node (ref "J5") (pin "2") (pinfunction "2_2") (pintype "passive"))
      (node (ref "J7") (pin "2") (pinfunction "2_2") (pintype "passive"))
      (node (ref "R1") (pin "2") (pinfunction "2_2") (pintype "passive"))
      (node (ref "R2") (pin "2") (pinfunction "2_2") (pintype "passive"))
      (node (ref "RA") (pin "1") (pinfunction "1_1") (pintype "passive"))
      (node (ref "RL") (pin "1") (pinfunction "1_1") (pintype "passive"))
      (node (ref "RS08") (pin "2") (pinfunction "2_2") (pintype "passive"))
    )
    (net (code "150") (name "WLS") (class "Default")
      (node (ref "IC37") (pin "4") (pinfunction "A2_4") (pintype "input"))
      (node (ref "IC9") (pin "5") (pinfunction "Q_5") (pintype "output"))
    )
    (net (code "151") (name "WRITING") (class "Default")
      (node (ref "IC10") (pin "5") (pinfunction "Q_5") (pintype "output"))
      (node (ref "IC41") (pin "13") (pinfunction "B_13") (pintype "input"))
      (node (ref "IC41") (pin "14") (pinfunction "A_14") (pintype "input"))
      (node (ref "IC6") (pin "2") (pinfunction "A_2") (pintype "input"))
      (node (ref "RS08") (pin "18") (pinfunction "18_18") (pintype "passive"))
    )
    (net (code "152") (name "unconnected-(C35L-Pad20)") (class "Default")
      (node (ref "C35L") (pin "20") (pinfunction "20_20") (pintype "passive"))
    )
    (net (code "153") (name "unconnected-(C35L-Pad40)") (class "Default")
      (node (ref "C35L") (pin "40") (pinfunction "40_40") (pintype "passive"))
    )
    (net (code "154") (name "unconnected-(C36L-Pad20)") (class "Default")
      (node (ref "C36L") (pin "20") (pinfunction "20_20") (pintype "passive"))
    )
    (net (code "155") (name "unconnected-(C36L-Pad40)") (class "Default")
      (node (ref "C36L") (pin "40") (pinfunction "40_40") (pintype "passive"))
    )
    (net (code "156") (name "unconnected-(D34L-Pad20)") (class "Default")
      (node (ref "D34L") (pin "20") (pinfunction "20_20") (pintype "passive"))
    )
    (net (code "157") (name "unconnected-(D34L-Pad36)") (class "Default")
      (node (ref "D34L") (pin "36") (pinfunction "36_36") (pintype "passive"))
    )
    (net (code "158") (name "unconnected-(D34L-Pad38)") (class "Default")
      (node (ref "D34L") (pin "38") (pinfunction "38_38") (pintype "passive"))
    )
    (net (code "159") (name "unconnected-(D34L-Pad40)") (class "Default")
      (node (ref "D34L") (pin "40") (pinfunction "40_40") (pintype "passive"))
    )
    (net (code "160") (name "unconnected-(D35L-Pad20)") (class "Default")
      (node (ref "D35L") (pin "20") (pinfunction "20_20") (pintype "passive"))
    )
    (net (code "161") (name "unconnected-(D35L-Pad40)") (class "Default")
      (node (ref "D35L") (pin "40") (pinfunction "40_40") (pintype "passive"))
    )
    (net (code "162") (name "unconnected-(D36L-Pad20)") (class "Default")
      (node (ref "D36L") (pin "20") (pinfunction "20_20") (pintype "passive"))
    )
    (net (code "163") (name "unconnected-(D36L-Pad40)") (class "Default")
      (node (ref "D36L") (pin "40") (pinfunction "40_40") (pintype "passive"))
    )
    (net (code "164") (name "unconnected-(DAR4-7A-BO-Pad13)") (class "Default")
      (node (ref "DAR4-7") (pin "13") (pinfunction "BO_13") (pintype "output"))
    )
    (net (code "165") (name "unconnected-(DAR4-7A-CO-Pad12)") (class "Default")
      (node (ref "DAR4-7") (pin "12") (pinfunction "CO_12") (pintype "output"))
    )
    (net (code "166") (name "unconnected-(DAR8-11A-BO-Pad13)") (class "Default")
      (node (ref "DAR8-11") (pin "13") (pinfunction "BO_13") (pintype "output"))
    )
    (net (code "167") (name "unconnected-(DMA0-3A-BO-Pad13)") (class "Default")
      (node (ref "DMA0-3") (pin "13") (pinfunction "BO_13") (pintype "output"))
    )
    (net (code "168") (name "unconnected-(DMA4-7A-BO-Pad13)") (class "Default")
      (node (ref "DMA4-7") (pin "13") (pinfunction "BO_13") (pintype "output"))
    )
    (net (code "169") (name "unconnected-(DMA8-11A-BO-Pad13)") (class "Default")
      (node (ref "DMA8-11") (pin "13") (pinfunction "BO_13") (pintype "output"))
    )
    (net (code "170") (name "unconnected-(FIELDA-BO-Pad13)") (class "Default")
      (node (ref "FIELD") (pin "13") (pinfunction "BO_13") (pintype "output"))
    )
    (net (code "171") (name "unconnected-(FIELDA-CO-Pad12)") (class "Default")
      (node (ref "FIELD") (pin "12") (pinfunction "CO_12") (pintype "output"))
    )
    (net (code "172") (name "unconnected-(FIELDA-QD-Pad7)") (class "Default")
      (node (ref "FIELD") (pin "7") (pinfunction "QD_7") (pintype "output"))
    )
    (net (code "173") (name "unconnected-(IC1A-W-Pad6)") (class "Default")
      (node (ref "IC1") (pin "6") (pinfunction "W_6") (pintype "output"))
    )
    (net (code "174") (name "unconnected-(IC2A-W-Pad6)") (class "Default")
      (node (ref "IC2") (pin "6") (pinfunction "W_6") (pintype "output"))
    )
    (net (code "175") (name "unconnected-(IC3A-W-Pad6)") (class "Default")
      (node (ref "IC3") (pin "6") (pinfunction "W_6") (pintype "output"))
    )
    (net (code "176") (name "unconnected-(IC4A-W-Pad6)") (class "Default")
      (node (ref "IC4") (pin "6") (pinfunction "W_6") (pintype "output"))
    )
    (net (code "177") (name "unconnected-(IC6A-Y0-Pad4)") (class "Default")
      (node (ref "IC6") (pin "4") (pinfunction "Y0_4") (pintype "output"))
    )
    (net (code "178") (name "unconnected-(IC6A-Y2-Pad6)") (class "Default")
      (node (ref "IC6") (pin "6") (pinfunction "Y2_6") (pintype "output"))
    )
    (net (code "179") (name "unconnected-(IC7A-Y0-Pad4)") (class "Default")
      (node (ref "IC7") (pin "4") (pinfunction "Y0_4") (pintype "output"))
    )
    (net (code "180") (name "unconnected-(IC7A-Y2-Pad6)") (class "Default")
      (node (ref "IC7") (pin "6") (pinfunction "Y2_6") (pintype "output"))
    )
    (net (code "181") (name "unconnected-(IC7A-Y3-Pad7)") (class "Default")
      (node (ref "IC7") (pin "7") (pinfunction "Y3_7") (pintype "output"))
    )
    (net (code "182") (name "unconnected-(IC7B-Y1-Pad11)") (class "Default")
      (node (ref "IC7") (pin "11") (pinfunction "Y1_11") (pintype "output"))
    )
    (net (code "183") (name "unconnected-(IC7B-Y2-Pad10)") (class "Default")
      (node (ref "IC7") (pin "10") (pinfunction "Y2_10") (pintype "output"))
    )
    (net (code "184") (name "unconnected-(IC7B-Y3-Pad9)") (class "Default")
      (node (ref "IC7") (pin "9") (pinfunction "Y3_9") (pintype "output"))
    )
    (net (code "185") (name "unconnected-(IC10A-~{Q}-Pad6)") (class "Default")
      (node (ref "IC10") (pin "6") (pinfunction "~{Q}_6") (pintype "output"))
    )
    (net (code "186") (name "unconnected-(IC11A-Q-Pad5)") (class "Default")
      (node (ref "IC11") (pin "5") (pinfunction "Q_5") (pintype "output"))
    )
    (net (code "187") (name "unconnected-(IC11B-~{Q}-Pad8)") (class "Default")
      (node (ref "IC11") (pin "8") (pinfunction "~{Q}_8") (pintype "output"))
    )
    (net (code "188") (name "unconnected-(IC13A-ODD-Pad6)") (class "Default")
      (node (ref "IC13") (pin "6") (pinfunction "ODD_6") (pintype "output"))
    )
    (net (code "189") (name "unconnected-(IC14A-EVN-Pad5)") (class "Default")
      (node (ref "IC14") (pin "5") (pinfunction "EVN_5") (pintype "output"))
    )
    (net (code "190") (name "unconnected-(IC15A-EVN-Pad5)") (class "Default")
      (node (ref "IC15") (pin "5") (pinfunction "EVN_5") (pintype "output"))
    )
    (net (code "191") (name "unconnected-(IC16A-Y1-Pad5)") (class "Default")
      (node (ref "IC16") (pin "5") (pinfunction "Y1_5") (pintype "output"))
    )
    (net (code "192") (name "unconnected-(IC16A-Y2-Pad6)") (class "Default")
      (node (ref "IC16") (pin "6") (pinfunction "Y2_6") (pintype "output"))
    )
    (net (code "193") (name "unconnected-(IC16A-Y3-Pad7)") (class "Default")
      (node (ref "IC16") (pin "7") (pinfunction "Y3_7") (pintype "output"))
    )
    (net (code "194") (name "unconnected-(IC16B-Y2-Pad10)") (class "Default")
      (node (ref "IC16") (pin "10") (pinfunction "Y2_10") (pintype "output"))
    )
    (net (code "195") (name "unconnected-(IC16B-Y3-Pad9)") (class "Default")
      (node (ref "IC16") (pin "9") (pinfunction "Y3_9") (pintype "output"))
    )
    (net (code "196") (name "unconnected-(IC17A-Y1-Pad5)") (class "Default")
      (node (ref "IC17") (pin "5") (pinfunction "Y1_5") (pintype "output"))
    )
    (net (code "197") (name "unconnected-(IC17A-Y2-Pad6)") (class "Default")
      (node (ref "IC17") (pin "6") (pinfunction "Y2_6") (pintype "output"))
    )
    (net (code "198") (name "unconnected-(IC17A-Y3-Pad7)") (class "Default")
      (node (ref "IC17") (pin "7") (pinfunction "Y3_7") (pintype "output"))
    )
    (net (code "199") (name "unconnected-(IC17B-Y2-Pad10)") (class "Default")
      (node (ref "IC17") (pin "10") (pinfunction "Y2_10") (pintype "output"))
    )
    (net (code "200") (name "unconnected-(IC17B-Y3-Pad9)") (class "Default")
      (node (ref "IC17") (pin "9") (pinfunction "Y3_9") (pintype "output"))
    )
    (net (code "201") (name "unconnected-(IC20B-Y4-Pad3)") (class "Default")
      (node (ref "IC20") (pin "3") (pinfunction "Y4_3") (pintype "tri_state"))
    )
    (net (code "202") (name "unconnected-(IC21B-Y0-Pad12)") (class "Default")
      (node (ref "IC21") (pin "12") (pinfunction "Y0_12") (pintype "output"))
    )
    (net (code "203") (name "unconnected-(IC21B-Y1-Pad11)") (class "Default")
      (node (ref "IC21") (pin "11") (pinfunction "Y1_11") (pintype "output"))
    )
    (net (code "204") (name "unconnected-(IC21B-Y2-Pad10)") (class "Default")
      (node (ref "IC21") (pin "10") (pinfunction "Y2_10") (pintype "output"))
    )
    (net (code "205") (name "unconnected-(IC25A-Y3-Pad12)") (class "Default")
      (node (ref "IC25") (pin "12") (pinfunction "Y3_12") (pintype "output"))
    )
    (net (code "206") (name "unconnected-(IC25A-Y5-Pad10)") (class "Default")
      (node (ref "IC25") (pin "10") (pinfunction "Y5_10") (pintype "output"))
    )
    (net (code "207") (name "unconnected-(IC25A-Y6-Pad9)") (class "Default")
      (node (ref "IC25") (pin "9") (pinfunction "Y6_9") (pintype "output"))
    )
    (net (code "208") (name "unconnected-(IC25A-Y7-Pad7)") (class "Default")
      (node (ref "IC25") (pin "7") (pinfunction "Y7_7") (pintype "output"))
    )
    (net (code "209") (name "unconnected-(IC27-Pad1)") (class "Default")
      (node (ref "IC27") (pin "1") (pinfunction "1_1") (pintype "passive"))
    )
    (net (code "210") (name "unconnected-(IC27-Pad2)") (class "Default")
      (node (ref "IC27") (pin "2") (pinfunction "2_2") (pintype "passive"))
    )
    (net (code "211") (name "unconnected-(IC27-Pad3)") (class "Default")
      (node (ref "IC27") (pin "3") (pinfunction "3_3") (pintype "passive"))
    )
    (net (code "212") (name "unconnected-(IC27-Pad4)") (class "Default")
      (node (ref "IC27") (pin "4") (pinfunction "4_4") (pintype "passive"))
    )
    (net (code "213") (name "unconnected-(IC27-Pad5)") (class "Default")
      (node (ref "IC27") (pin "5") (pinfunction "5_5") (pintype "passive"))
    )
    (net (code "214") (name "unconnected-(IC27-Pad6)") (class "Default")
      (node (ref "IC27") (pin "6") (pinfunction "6_6") (pintype "passive"))
    )
    (net (code "215") (name "unconnected-(IC27-Pad7)") (class "Default")
      (node (ref "IC27") (pin "7") (pinfunction "7_7") (pintype "passive"))
    )
    (net (code "216") (name "unconnected-(IC27-Pad8)") (class "Default")
      (node (ref "IC27") (pin "8") (pinfunction "8_8") (pintype "passive"))
    )
    (net (code "217") (name "unconnected-(IC27-Pad9)") (class "Default")
      (node (ref "IC27") (pin "9") (pinfunction "9_9") (pintype "passive"))
    )
    (net (code "218") (name "unconnected-(IC27-Pad10)") (class "Default")
      (node (ref "IC27") (pin "10") (pinfunction "10_10") (pintype "passive"))
    )
    (net (code "219") (name "unconnected-(IC27-Pad11)") (class "Default")
      (node (ref "IC27") (pin "11") (pinfunction "11_11") (pintype "passive"))
    )
    (net (code "220") (name "unconnected-(IC27-Pad12)") (class "Default")
      (node (ref "IC27") (pin "12") (pinfunction "12_12") (pintype "passive"))
    )
    (net (code "221") (name "unconnected-(IC27-Pad13)") (class "Default")
      (node (ref "IC27") (pin "13") (pinfunction "13_13") (pintype "passive"))
    )
    (net (code "222") (name "unconnected-(IC27-Pad14)") (class "Default")
      (node (ref "IC27") (pin "14") (pinfunction "14_14") (pintype "passive"))
    )
    (net (code "223") (name "unconnected-(IC27-Pad15)") (class "Default")
      (node (ref "IC27") (pin "15") (pinfunction "15_15") (pintype "passive"))
    )
    (net (code "224") (name "unconnected-(IC27-Pad16)") (class "Default")
      (node (ref "IC27") (pin "16") (pinfunction "16_16") (pintype "passive"))
    )
    (net (code "225") (name "unconnected-(IC27-Pad17)") (class "Default")
      (node (ref "IC27") (pin "17") (pinfunction "17_17") (pintype "passive"))
    )
    (net (code "226") (name "unconnected-(IC27-Pad18)") (class "Default")
      (node (ref "IC27") (pin "18") (pinfunction "18_18") (pintype "passive"))
    )
    (net (code "227") (name "unconnected-(IC27-Pad19)") (class "Default")
      (node (ref "IC27") (pin "19") (pinfunction "19_19") (pintype "passive"))
    )
    (net (code "228") (name "unconnected-(IC27-Pad20)") (class "Default")
      (node (ref "IC27") (pin "20") (pinfunction "20_20") (pintype "passive"))
    )
    (net (code "229") (name "unconnected-(IC29A-Y3-Pad12)") (class "Default")
      (node (ref "IC29") (pin "12") (pinfunction "Y3_12") (pintype "output"))
    )
    (net (code "230") (name "unconnected-(IC29A-Y5-Pad10)") (class "Default")
      (node (ref "IC29") (pin "10") (pinfunction "Y5_10") (pintype "output"))
    )
    (net (code "231") (name "unconnected-(IC29A-Y6-Pad9)") (class "Default")
      (node (ref "IC29") (pin "9") (pinfunction "Y6_9") (pintype "output"))
    )
    (net (code "232") (name "unconnected-(IC29A-Y7-Pad7)") (class "Default")
      (node (ref "IC29") (pin "7") (pinfunction "Y7_7") (pintype "output"))
    )
    (net (code "233") (name "unconnected-(IC32A-Y3-Pad12)") (class "Default")
      (node (ref "IC32") (pin "12") (pinfunction "Y3_12") (pintype "output"))
    )
    (net (code "234") (name "unconnected-(IC32A-Y5-Pad10)") (class "Default")
      (node (ref "IC32") (pin "10") (pinfunction "Y5_10") (pintype "output"))
    )
    (net (code "235") (name "unconnected-(IC32A-Y6-Pad9)") (class "Default")
      (node (ref "IC32") (pin "9") (pinfunction "Y6_9") (pintype "output"))
    )
    (net (code "236") (name "unconnected-(IC32A-Y7-Pad7)") (class "Default")
      (node (ref "IC32") (pin "7") (pinfunction "Y7_7") (pintype "output"))
    )
    (net (code "237") (name "unconnected-(IC35B-Y2-Pad7)") (class "Default")
      (node (ref "IC35") (pin "7") (pinfunction "Y2_7") (pintype "tri_state"))
    )
    (net (code "238") (name "unconnected-(IC35B-Y3-Pad5)") (class "Default")
      (node (ref "IC35") (pin "5") (pinfunction "Y3_5") (pintype "tri_state"))
    )
    (net (code "239") (name "unconnected-(IC35B-Y4-Pad3)") (class "Default")
      (node (ref "IC35") (pin "3") (pinfunction "Y4_3") (pintype "tri_state"))
    )
    (net (code "240") (name "unconnected-(IC41A-Y1-Pad5)") (class "Default")
      (node (ref "IC41") (pin "5") (pinfunction "Y1_5") (pintype "output"))
    )
    (net (code "241") (name "unconnected-(IC41A-Y2-Pad6)") (class "Default")
      (node (ref "IC41") (pin "6") (pinfunction "Y2_6") (pintype "output"))
    )
    (net (code "242") (name "unconnected-(IC41B-Y1-Pad11)") (class "Default")
      (node (ref "IC41") (pin "11") (pinfunction "Y1_11") (pintype "output"))
    )
    (net (code "243") (name "unconnected-(IC41B-Y2-Pad10)") (class "Default")
      (node (ref "IC41") (pin "10") (pinfunction "Y2_10") (pintype "output"))
    )
    (net (code "244") (name "unconnected-(INTENBA-BO-Pad13)") (class "Default")
      (node (ref "INTENB") (pin "13") (pinfunction "BO_13") (pintype "output"))
    )
    (net (code "245") (name "unconnected-(INTENBA-CO-Pad12)") (class "Default")
      (node (ref "INTENB") (pin "12") (pinfunction "CO_12") (pintype "output"))
    )
    (net (code "246") (name "unconnected-(INTENBA-QD-Pad7)") (class "Default")
      (node (ref "INTENB") (pin "7") (pinfunction "QD_7") (pintype "output"))
    )
    (net (code "247") (name "~{3CYC}") (class "Default")
      (node (ref "C35L") (pin "28") (pinfunction "28_28") (pintype "passive"))
      (node (ref "J2") (pin "1") (pinfunction "1_1") (pintype "passive"))
    )
    (net (code "248") (name "~{601}") (class "Default")
      (node (ref "IC11") (pin "13") (pinfunction "CLR_13") (pintype "input"))
      (node (ref "IC18") (pin "4") (pinfunction "I0_4") (pintype "input"))
      (node (ref "IC18") (pin "5") (pinfunction "I1_5") (pintype "input"))
      (node (ref "IC23") (pin "1") (pinfunction "CLR_1") (pintype "input"))
      (node (ref "IC32") (pin "15") (pinfunction "Y0_15") (pintype "output"))
      (node (ref "IC9") (pin "1") (pinfunction "CLR_1") (pintype "input"))
      (node (ref "IC9") (pin "13") (pinfunction "CLR_13") (pintype "input"))
    )
    (net (code "249") (name "~{602}") (class "Default")
      (node (ref "IC10") (pin "1") (pinfunction "CLR_1") (pintype "input"))
      (node (ref "IC18") (pin "1") (pinfunction "I0_1") (pintype "input"))
      (node (ref "IC18") (pin "12") (pinfunction "I0_12") (pintype "input"))
      (node (ref "IC29") (pin "15") (pinfunction "Y0_15") (pintype "output"))
    )
    (net (code "250") (name "~{604}") (class "Default")
      (node (ref "IC10") (pin "4") (pinfunction "PRE_4") (pintype "input"))
      (node (ref "IC18") (pin "13") (pinfunction "I1_13") (pintype "input"))
      (node (ref "IC18") (pin "2") (pinfunction "I1_2") (pintype "input"))
      (node (ref "IC25") (pin "15") (pinfunction "Y0_15") (pintype "output"))
    )
    (net (code "251") (name "~{611}") (class "Default")
      (node (ref "FIELD") (pin "14") (pinfunction "CLR_14") (pintype "input"))
      (node (ref "IC32") (pin "14") (pinfunction "Y1_14") (pintype "output"))
      (node (ref "INTENB") (pin "14") (pinfunction "CLR_14") (pintype "input"))
    )
    (net (code "252") (name "~{612}") (class "Default")
      (node (ref "IC19") (pin "5") (pinfunction "I_5") (pintype "input"))
      (node (ref "IC29") (pin "14") (pinfunction "Y1_14") (pintype "output"))
    )
    (net (code "253") (name "~{614}") (class "Default")
      (node (ref "IC17") (pin "13") (pinfunction "B_13") (pintype "input"))
      (node (ref "IC22") (pin "3") (pinfunction "I_3") (pintype "input"))
      (node (ref "IC25") (pin "14") (pinfunction "Y1_14") (pintype "output"))
    )
    (net (code "254") (name "~{621}") (class "Default")
      (node (ref "IC32") (pin "13") (pinfunction "Y2_13") (pintype "output"))
      (node (ref "IC7") (pin "3") (pinfunction "B_3") (pintype "input"))
    )
    (net (code "255") (name "~{622}") (class "Default")
      (node (ref "IC29") (pin "13") (pinfunction "Y2_13") (pintype "output"))
      (node (ref "IC7") (pin "13") (pinfunction "B_13") (pintype "input"))
    )
    (net (code "256") (name "~{624}") (class "Default")
      (node (ref "IC22") (pin "13") (pinfunction "I_13") (pintype "input"))
      (node (ref "IC24") (pin "1") (pinfunction "G_1") (pintype "input"))
      (node (ref "IC25") (pin "13") (pinfunction "Y2_13") (pintype "output"))
      (node (ref "IC31") (pin "1") (pinfunction "G_1") (pintype "input"))
      (node (ref "IC38") (pin "1") (pinfunction "G_1") (pintype "input"))
    )
    (net (code "257") (name "~{641}") (class "Default")
      (node (ref "IC16") (pin "13") (pinfunction "B_13") (pintype "input"))
      (node (ref "IC32") (pin "11") (pinfunction "Y4_11") (pintype "output"))
    )
    (net (code "258") (name "~{642}") (class "Default")
      (node (ref "DAR4-7") (pin "11") (pinfunction "LD_11") (pintype "input"))
      (node (ref "DAR8-11") (pin "11") (pinfunction "LD_11") (pintype "input"))
      (node (ref "IC29") (pin "11") (pinfunction "Y4_11") (pintype "output"))
    )
    (net (code "259") (name "~{644}") (class "Default")
      (node (ref "IC16") (pin "3") (pinfunction "B_3") (pintype "input"))
      (node (ref "IC25") (pin "11") (pinfunction "Y4_11") (pintype "output"))
    )
    (net (code "260") (name "~{645}") (class "Default")
      (node (ref "IC16") (pin "4") (pinfunction "Y0_4") (pintype "output"))
      (node (ref "IC24") (pin "19") (pinfunction "G_19") (pintype "input"))
      (node (ref "IC31") (pin "19") (pinfunction "G_19") (pintype "input"))
      (node (ref "IC38") (pin "19") (pinfunction "G_19") (pintype "input"))
    )
    (net (code "261") (name "~{ACB00}") (class "Default")
      (node (ref "D34L") (pin "2") (pinfunction "2_2") (pintype "passive"))
      (node (ref "IC37") (pin "12") (pinfunction "Y4_12") (pintype "tri_state"))
      (node (ref "IC38") (pin "12") (pinfunction "Y4_12") (pintype "tri_state"))
      (node (ref "IC38") (pin "3") (pinfunction "Y4_3") (pintype "tri_state"))
    )
    (net (code "262") (name "~{ACB01}") (class "Default")
      (node (ref "D34L") (pin "4") (pinfunction "4_4") (pintype "passive"))
      (node (ref "IC37") (pin "14") (pinfunction "Y3_14") (pintype "tri_state"))
      (node (ref "IC38") (pin "14") (pinfunction "Y3_14") (pintype "tri_state"))
      (node (ref "IC38") (pin "5") (pinfunction "Y3_5") (pintype "tri_state"))
    )
    (net (code "263") (name "~{ACB02}") (class "Default")
      (node (ref "D34L") (pin "6") (pinfunction "6_6") (pintype "passive"))
      (node (ref "IC37") (pin "16") (pinfunction "Y2_16") (pintype "tri_state"))
      (node (ref "IC38") (pin "16") (pinfunction "Y2_16") (pintype "tri_state"))
      (node (ref "IC38") (pin "7") (pinfunction "Y2_7") (pintype "tri_state"))
    )
    (net (code "264") (name "~{ACB03}") (class "Default")
      (node (ref "D34L") (pin "8") (pinfunction "8_8") (pintype "passive"))
      (node (ref "IC37") (pin "18") (pinfunction "Y1_18") (pintype "tri_state"))
      (node (ref "IC38") (pin "18") (pinfunction "Y1_18") (pintype "tri_state"))
      (node (ref "IC38") (pin "9") (pinfunction "Y1_9") (pintype "tri_state"))
    )
    (net (code "265") (name "~{ACB04}") (class "Default")
      (node (ref "D34L") (pin "10") (pinfunction "10_10") (pintype "passive"))
      (node (ref "IC30") (pin "3") (pinfunction "Y4_3") (pintype "tri_state"))
      (node (ref "IC31") (pin "12") (pinfunction "Y4_12") (pintype "tri_state"))
      (node (ref "IC31") (pin "3") (pinfunction "Y4_3") (pintype "tri_state"))
    )
    (net (code "266") (name "~{ACB05}") (class "Default")
      (node (ref "D34L") (pin "12") (pinfunction "12_12") (pintype "passive"))
      (node (ref "IC30") (pin "5") (pinfunction "Y3_5") (pintype "tri_state"))
      (node (ref "IC31") (pin "14") (pinfunction "Y3_14") (pintype "tri_state"))
      (node (ref "IC31") (pin "5") (pinfunction "Y3_5") (pintype "tri_state"))
    )
    (net (code "267") (name "~{ACB06}") (class "Default")
      (node (ref "D34L") (pin "14") (pinfunction "14_14") (pintype "passive"))
      (node (ref "IC30") (pin "7") (pinfunction "Y2_7") (pintype "tri_state"))
      (node (ref "IC31") (pin "16") (pinfunction "Y2_16") (pintype "tri_state"))
      (node (ref "IC31") (pin "7") (pinfunction "Y2_7") (pintype "tri_state"))
    )
    (net (code "268") (name "~{ACB07}") (class "Default")
      (node (ref "D34L") (pin "16") (pinfunction "16_16") (pintype "passive"))
      (node (ref "IC30") (pin "9") (pinfunction "Y1_9") (pintype "tri_state"))
      (node (ref "IC31") (pin "18") (pinfunction "Y1_18") (pintype "tri_state"))
      (node (ref "IC31") (pin "9") (pinfunction "Y1_9") (pintype "tri_state"))
    )
    (net (code "269") (name "~{ACB08}") (class "Default")
      (node (ref "D34L") (pin "18") (pinfunction "18_18") (pintype "passive"))
      (node (ref "IC24") (pin "12") (pinfunction "Y4_12") (pintype "tri_state"))
      (node (ref "IC24") (pin "3") (pinfunction "Y4_3") (pintype "tri_state"))
      (node (ref "IC30") (pin "12") (pinfunction "Y4_12") (pintype "tri_state"))
    )
    (net (code "270") (name "~{ACB09}") (class "Default")
      (node (ref "D34L") (pin "22") (pinfunction "22_22") (pintype "passive"))
      (node (ref "IC24") (pin "14") (pinfunction "Y3_14") (pintype "tri_state"))
      (node (ref "IC24") (pin "5") (pinfunction "Y3_5") (pintype "tri_state"))
      (node (ref "IC30") (pin "14") (pinfunction "Y3_14") (pintype "tri_state"))
    )
    (net (code "271") (name "~{ACB10}") (class "Default")
      (node (ref "D34L") (pin "24") (pinfunction "24_24") (pintype "passive"))
      (node (ref "IC24") (pin "16") (pinfunction "Y2_16") (pintype "tri_state"))
      (node (ref "IC24") (pin "7") (pinfunction "Y2_7") (pintype "tri_state"))
      (node (ref "IC30") (pin "16") (pinfunction "Y2_16") (pintype "tri_state"))
    )
    (net (code "272") (name "~{ACB11}") (class "Default")
      (node (ref "D34L") (pin "26") (pinfunction "26_26") (pintype "passive"))
      (node (ref "IC24") (pin "18") (pinfunction "Y1_18") (pintype "tri_state"))
      (node (ref "IC24") (pin "9") (pinfunction "Y1_9") (pintype "tri_state"))
      (node (ref "IC30") (pin "18") (pinfunction "Y1_18") (pintype "tri_state"))
    )
    (net (code "273") (name "~{ACCLEAR}") (class "Default")
      (node (ref "D34L") (pin "32") (pinfunction "32_32") (pintype "passive"))
      (node (ref "IC22") (pin "12") (pinfunction "O_12") (pintype "open_collector"))
      (node (ref "IC22") (pin "2") (pinfunction "O_2") (pintype "open_collector"))
      (node (ref "IC22") (pin "4") (pinfunction "O_4") (pintype "open_collector"))
    )
    (net (code "274") (name "~{BADDAC}") (class "Default")
      (node (ref "C36L") (pin "34") (pinfunction "34_34") (pintype "passive"))
      (node (ref "IC11") (pin "1") (pinfunction "CLR_1") (pintype "input"))
    )
    (net (code "275") (name "~{BBREAK}") (class "Default")
      (node (ref "C36L") (pin "32") (pinfunction "32_32") (pintype "passive"))
      (node (ref "DMA8-11") (pin "5") (pinfunction "UP_5") (pintype "input"))
      (node (ref "IC20") (pin "19") (pinfunction "G_19") (pintype "input"))
      (node (ref "IC21") (pin "15") (pinfunction "G_15") (pintype "input"))
      (node (ref "IC41") (pin "1") (pinfunction "G_1") (pintype "input"))
      (node (ref "IC41") (pin "15") (pinfunction "G_15") (pintype "input"))
      (node (ref "IC6") (pin "1") (pinfunction "G_1") (pintype "input"))
    )
    (net (code "276") (name "~{BMB03}") (class "Default")
      (node (ref "D35L") (pin "8") (pinfunction "8_8") (pintype "passive"))
    )
    (net (code "277") (name "~{BMB04}") (class "Default")
      (node (ref "D35L") (pin "12") (pinfunction "12_12") (pintype "passive"))
    )
    (net (code "278") (name "~{BMB05}") (class "Default")
      (node (ref "D35L") (pin "16") (pinfunction "16_16") (pintype "passive"))
    )
    (net (code "279") (name "~{BMB06}") (class "Default")
      (node (ref "D35L") (pin "22") (pinfunction "22_22") (pintype "passive"))
    )
    (net (code "280") (name "~{BMB07}") (class "Default")
      (node (ref "D35L") (pin "26") (pinfunction "26_26") (pintype "passive"))
    )
    (net (code "281") (name "~{BMB08}") (class "Default")
      (node (ref "D35L") (pin "30") (pinfunction "30_30") (pintype "passive"))
    )
    (net (code "282") (name "~{BRK_RQ}") (class "Default")
      (node (ref "C36L") (pin "28") (pinfunction "28_28") (pintype "passive"))
      (node (ref "IC11") (pin "6") (pinfunction "~{Q}_6") (pintype "output"))
    )
    (net (code "283") (name "~{BRUN}") (class "Default")
      (node (ref "D34L") (pin "34") (pinfunction "34_34") (pintype "passive"))
    )
    (net (code "284") (name "~{BWCO}") (class "Default")
      (node (ref "C35L") (pin "32") (pinfunction "32_32") (pintype "passive"))
      (node (ref "IC10") (pin "13") (pinfunction "CLR_13") (pintype "input"))
      (node (ref "IC11") (pin "12") (pinfunction "D_12") (pintype "input"))
    )
    (net (code "285") (name "~{DA00}") (class "Default")
      (node (ref "C36L") (pin "2") (pinfunction "2_2") (pintype "passive"))
      (node (ref "J14") (pin "1") (pinfunction "1_1") (pintype "passive"))
    )
    (net (code "286") (name "~{DA01}") (class "Default")
      (node (ref "C36L") (pin "4") (pinfunction "4_4") (pintype "passive"))
      (node (ref "J13") (pin "1") (pinfunction "1_1") (pintype "passive"))
    )
    (net (code "287") (name "~{DA02}") (class "Default")
      (node (ref "C36L") (pin "6") (pinfunction "6_6") (pintype "passive"))
      (node (ref "J12") (pin "1") (pinfunction "1_1") (pintype "passive"))
    )
    (net (code "288") (name "~{DA03}") (class "Default")
      (node (ref "C36L") (pin "8") (pinfunction "8_8") (pintype "passive"))
      (node (ref "J11") (pin "1") (pinfunction "1_1") (pintype "passive"))
    )
    (net (code "289") (name "~{DA04}") (class "Default")
      (node (ref "C36L") (pin "10") (pinfunction "10_10") (pintype "passive"))
      (node (ref "J10") (pin "1") (pinfunction "1_1") (pintype "passive"))
    )
    (net (code "290") (name "~{DA05}") (class "Default")
      (node (ref "C36L") (pin "12") (pinfunction "12_12") (pintype "passive"))
      (node (ref "J9") (pin "1") (pinfunction "1_1") (pintype "passive"))
    )
    (net (code "291") (name "~{DA06}") (class "Default")
      (node (ref "C36L") (pin "14") (pinfunction "14_14") (pintype "passive"))
      (node (ref "J8") (pin "1") (pinfunction "1_1") (pintype "passive"))
    )
    (net (code "292") (name "~{DA07}") (class "Default")
      (node (ref "C36L") (pin "16") (pinfunction "16_16") (pintype "passive"))
      (node (ref "J7") (pin "1") (pinfunction "1_1") (pintype "passive"))
    )
    (net (code "293") (name "~{DA08}") (class "Default")
      (node (ref "C36L") (pin "18") (pinfunction "18_18") (pintype "passive"))
      (node (ref "J6") (pin "1") (pinfunction "1_1") (pintype "passive"))
    )
    (net (code "294") (name "~{DA09}") (class "Default")
      (node (ref "C36L") (pin "22") (pinfunction "22_22") (pintype "passive"))
      (node (ref "J5") (pin "1") (pinfunction "1_1") (pintype "passive"))
    )
    (net (code "295") (name "~{DA10}") (class "Default")
      (node (ref "C36L") (pin "24") (pinfunction "24_24") (pintype "passive"))
      (node (ref "J4") (pin "1") (pinfunction "1_1") (pintype "passive"))
    )
    (net (code "296") (name "~{DA11}") (class "Default")
      (node (ref "C36L") (pin "26") (pinfunction "26_26") (pintype "passive"))
      (node (ref "J3") (pin "1") (pinfunction "1_1") (pintype "passive"))
    )
    (net (code "297") (name "~{DATA00}") (class "Default")
      (node (ref "C35L") (pin "2") (pinfunction "2_2") (pintype "passive"))
      (node (ref "IC34") (pin "12") (pinfunction "Y4_12") (pintype "tri_state"))
    )
    (net (code "298") (name "~{DATA01}") (class "Default")
      (node (ref "C35L") (pin "4") (pinfunction "4_4") (pintype "passive"))
      (node (ref "IC34") (pin "14") (pinfunction "Y3_14") (pintype "tri_state"))
    )
    (net (code "299") (name "~{DATA02}") (class "Default")
      (node (ref "C35L") (pin "6") (pinfunction "6_6") (pintype "passive"))
      (node (ref "IC34") (pin "16") (pinfunction "Y2_16") (pintype "tri_state"))
    )
    (net (code "300") (name "~{DATA03}") (class "Default")
      (node (ref "C35L") (pin "8") (pinfunction "8_8") (pintype "passive"))
      (node (ref "IC34") (pin "18") (pinfunction "Y1_18") (pintype "tri_state"))
    )
    (net (code "301") (name "~{DATA04}") (class "Default")
      (node (ref "C35L") (pin "10") (pinfunction "10_10") (pintype "passive"))
      (node (ref "IC26") (pin "3") (pinfunction "Y4_3") (pintype "tri_state"))
    )
    (net (code "302") (name "~{DATA05}") (class "Default")
      (node (ref "C35L") (pin "12") (pinfunction "12_12") (pintype "passive"))
      (node (ref "IC26") (pin "5") (pinfunction "Y3_5") (pintype "tri_state"))
    )
    (net (code "303") (name "~{DATA06}") (class "Default")
      (node (ref "C35L") (pin "14") (pinfunction "14_14") (pintype "passive"))
      (node (ref "IC26") (pin "7") (pinfunction "Y2_7") (pintype "tri_state"))
    )
    (net (code "304") (name "~{DATA07}") (class "Default")
      (node (ref "C35L") (pin "16") (pinfunction "16_16") (pintype "passive"))
      (node (ref "IC26") (pin "9") (pinfunction "Y1_9") (pintype "tri_state"))
    )
    (net (code "305") (name "~{DATA08}") (class "Default")
      (node (ref "C35L") (pin "18") (pinfunction "18_18") (pintype "passive"))
      (node (ref "IC26") (pin "12") (pinfunction "Y4_12") (pintype "tri_state"))
    )
    (net (code "306") (name "~{DATA09}") (class "Default")
      (node (ref "C35L") (pin "22") (pinfunction "22_22") (pintype "passive"))
      (node (ref "IC26") (pin "14") (pinfunction "Y3_14") (pintype "tri_state"))
    )
    (net (code "307") (name "~{DATA10}") (class "Default")
      (node (ref "C35L") (pin "24") (pinfunction "24_24") (pintype "passive"))
      (node (ref "IC26") (pin "16") (pinfunction "Y2_16") (pintype "tri_state"))
    )
    (net (code "308") (name "~{DATA11}") (class "Default")
      (node (ref "C35L") (pin "26") (pinfunction "26_26") (pintype "passive"))
      (node (ref "IC26") (pin "18") (pinfunction "Y1_18") (pintype "tri_state"))
    )
    (net (code "309") (name "~{DCXA}") (class "Default")
      (node (ref "IC16") (pin "12") (pinfunction "Y0_12") (pintype "output"))
      (node (ref "IC18") (pin "10") (pinfunction "I1_10") (pintype "input"))
      (node (ref "IC18") (pin "9") (pinfunction "I0_9") (pintype "input"))
    )
    (net (code "310") (name "~{DIMA}") (class "Default")
      (node (ref "IC17") (pin "11") (pinfunction "Y1_11") (pintype "output"))
      (node (ref "IC30") (pin "1") (pinfunction "G_1") (pintype "input"))
      (node (ref "IC30") (pin "19") (pinfunction "G_19") (pintype "input"))
      (node (ref "IC37") (pin "1") (pinfunction "G_1") (pintype "input"))
    )
    (net (code "311") (name "~{DIML}") (class "Default")
      (node (ref "FIELD") (pin "11") (pinfunction "LD_11") (pintype "input"))
      (node (ref "IC17") (pin "12") (pinfunction "Y0_12") (pintype "output"))
      (node (ref "INTENB") (pin "11") (pinfunction "LD_11") (pintype "input"))
    )
    (net (code "312") (name "~{DMA-IN}") (class "Default")
      (node (ref "IC13") (pin "4") (pinfunction "OI_4") (pintype "input"))
      (node (ref "IC26") (pin "1") (pinfunction "G_1") (pintype "input"))
      (node (ref "IC26") (pin "19") (pinfunction "G_19") (pintype "input"))
      (node (ref "IC34") (pin "1") (pinfunction "G_1") (pintype "input"))
      (node (ref "IC41") (pin "12") (pinfunction "Y0_12") (pintype "output"))
    )
    (net (code "313") (name "~{DMA-OUT}") (class "Default")
      (node (ref "IC28") (pin "1") (pinfunction "G_1") (pintype "input"))
      (node (ref "IC28") (pin "19") (pinfunction "G_19") (pintype "input"))
      (node (ref "IC35") (pin "1") (pinfunction "G_1") (pintype "input"))
      (node (ref "IC35") (pin "19") (pinfunction "G_19") (pintype "input"))
      (node (ref "IC41") (pin "9") (pinfunction "Y3_9") (pintype "output"))
    )
    (net (code "314") (name "~{DRV01}") (class "Default")
      (node (ref "IC41") (pin "4") (pinfunction "Y0_4") (pintype "output"))
      (node (ref "RS08") (pin "38") (pinfunction "38_38") (pintype "passive"))
    )
    (net (code "315") (name "~{DRV23}") (class "Default")
      (node (ref "IC41") (pin "7") (pinfunction "Y3_7") (pintype "output"))
      (node (ref "RS08") (pin "22") (pinfunction "22_22") (pintype "passive"))
    )
    (net (code "316") (name "~{DRVOK}") (class "Default")
      (node (ref "IC21") (pin "13") (pinfunction "B_13") (pintype "input"))
      (node (ref "IC21") (pin "14") (pinfunction "A_14") (pintype "input"))
      (node (ref "R2") (pin "1") (pinfunction "1_1") (pintype "passive"))
      (node (ref "RS08") (pin "40") (pinfunction "40_40") (pintype "passive"))
    )
    (net (code "317") (name "~{EXAD0}") (class "Default")
      (node (ref "C35L") (pin "34") (pinfunction "34_34") (pintype "passive"))
      (node (ref "IC20") (pin "9") (pinfunction "Y1_9") (pintype "tri_state"))
    )
    (net (code "318") (name "~{EXAD1}") (class "Default")
      (node (ref "C35L") (pin "36") (pinfunction "36_36") (pintype "passive"))
      (node (ref "IC20") (pin "7") (pinfunction "Y2_7") (pintype "tri_state"))
    )
    (net (code "319") (name "~{EXAD2}") (class "Default")
      (node (ref "C35L") (pin "38") (pinfunction "38_38") (pintype "passive"))
      (node (ref "IC20") (pin "5") (pinfunction "Y3_5") (pintype "tri_state"))
    )
    (net (code "320") (name "~{INT_RQ}") (class "Default")
      (node (ref "D34L") (pin "30") (pinfunction "30_30") (pintype "passive"))
      (node (ref "IC40") (pin "3") (pinfunction "O_3") (pintype "open_collector"))
      (node (ref "IC40") (pin "6") (pinfunction "O_6") (pintype "open_collector"))
      (node (ref "IC40") (pin "8") (pinfunction "O_8") (pintype "open_collector"))
    )
    (net (code "321") (name "~{IOS}") (class "Default")
      (node (ref "D34L") (pin "28") (pinfunction "28_28") (pintype "passive"))
      (node (ref "IC22") (pin "10") (pinfunction "O_10") (pintype "open_collector"))
    )
    (net (code "322") (name "~{MEM_INC}") (class "Default")
      (node (ref "C36L") (pin "36") (pinfunction "36_36") (pintype "passive"))
    )
    (net (code "323") (name "~{MYDEV}") (class "Default")
      (node (ref "IC25") (pin "4") (pinfunction "G2A_4") (pintype "input"))
      (node (ref "IC29") (pin "4") (pinfunction "G2A_4") (pintype "input"))
      (node (ref "IC32") (pin "4") (pinfunction "G2A_4") (pintype "input"))
      (node (ref "PAD1") (pin "1") (pinfunction "P_1") (pintype "passive"))
    )
    (net (code "324") (name "~{NXD}") (class "Default")
      (node (ref "IC12") (pin "12") (pinfunction "I0_12") (pintype "input"))
      (node (ref "IC23") (pin "6") (pinfunction "~{Q}_6") (pintype "output"))
    )
    (net (code "325") (name "~{PER}") (class "Default")
      (node (ref "IC12") (pin "4") (pinfunction "I0_4") (pintype "input"))
      (node (ref "IC9") (pin "8") (pinfunction "~{Q}_8") (pintype "output"))
    )
    (net (code "326") (name "~{SETNXD}") (class "Default")
      (node (ref "IC21") (pin "9") (pinfunction "Y3_9") (pintype "output"))
      (node (ref "IC23") (pin "4") (pinfunction "PRE_4") (pintype "input"))
    )
    (net (code "327") (name "~{SETPER}") (class "Default")
      (node (ref "IC13") (pin "5") (pinfunction "EVN_5") (pintype "output"))
      (node (ref "IC9") (pin "10") (pinfunction "PRE_10") (pintype "input"))
    )
    (net (code "328") (name "~{SETWLS}") (class "Default")
      (node (ref "IC6") (pin "7") (pinfunction "Y3_7") (pintype "output"))
      (node (ref "IC9") (pin "4") (pinfunction "PRE_4") (pintype "input"))
    )
    (net (code "329") (name "~{SKIP}") (class "Default")
      (node (ref "IC17") (pin "2") (pinfunction "A_2") (pintype "input"))
      (node (ref "IC19") (pin "10") (pinfunction "O_10") (pintype "open_collector"))
      (node (ref "IC19") (pin "2") (pinfunction "O_2") (pintype "open_collector"))
      (node (ref "IC19") (pin "6") (pinfunction "O_6") (pintype "open_collector"))
      (node (ref "R1") (pin "1") (pinfunction "1_1") (pintype "passive"))
    )
    (net (code "330") (name "~{START}") (class "Default")
      (node (ref "DMA0-3") (pin "11") (pinfunction "LD_11") (pintype "input"))
      (node (ref "DMA4-7") (pin "11") (pinfunction "LD_11") (pintype "input"))
      (node (ref "DMA8-11") (pin "11") (pinfunction "LD_11") (pintype "input"))
      (node (ref "IC18") (pin "3") (pinfunction "O_3") (pintype "output"))
    )
    (net (code "331") (name "~{WE}") (class "Default")
      (node (ref "IC22") (pin "5") (pinfunction "I_5") (pintype "input"))
      (node (ref "IC6") (pin "5") (pinfunction "Y1_5") (pintype "output"))
      (node (ref "RS08") (pin "8") (pinfunction "8_8") (pintype "passive"))
    )
    (net (code "332") (name "~{WLS}") (class "Default")
      (node (ref "IC12") (pin "13") (pinfunction "I1_13") (pintype "input"))
      (node (ref "IC9") (pin "6") (pinfunction "~{Q}_6") (pintype "output"))
    )
  )
)
